# RFboardLeiden48_V_1_00.net
KiCad netlist of a schematic drawn in EAGLE
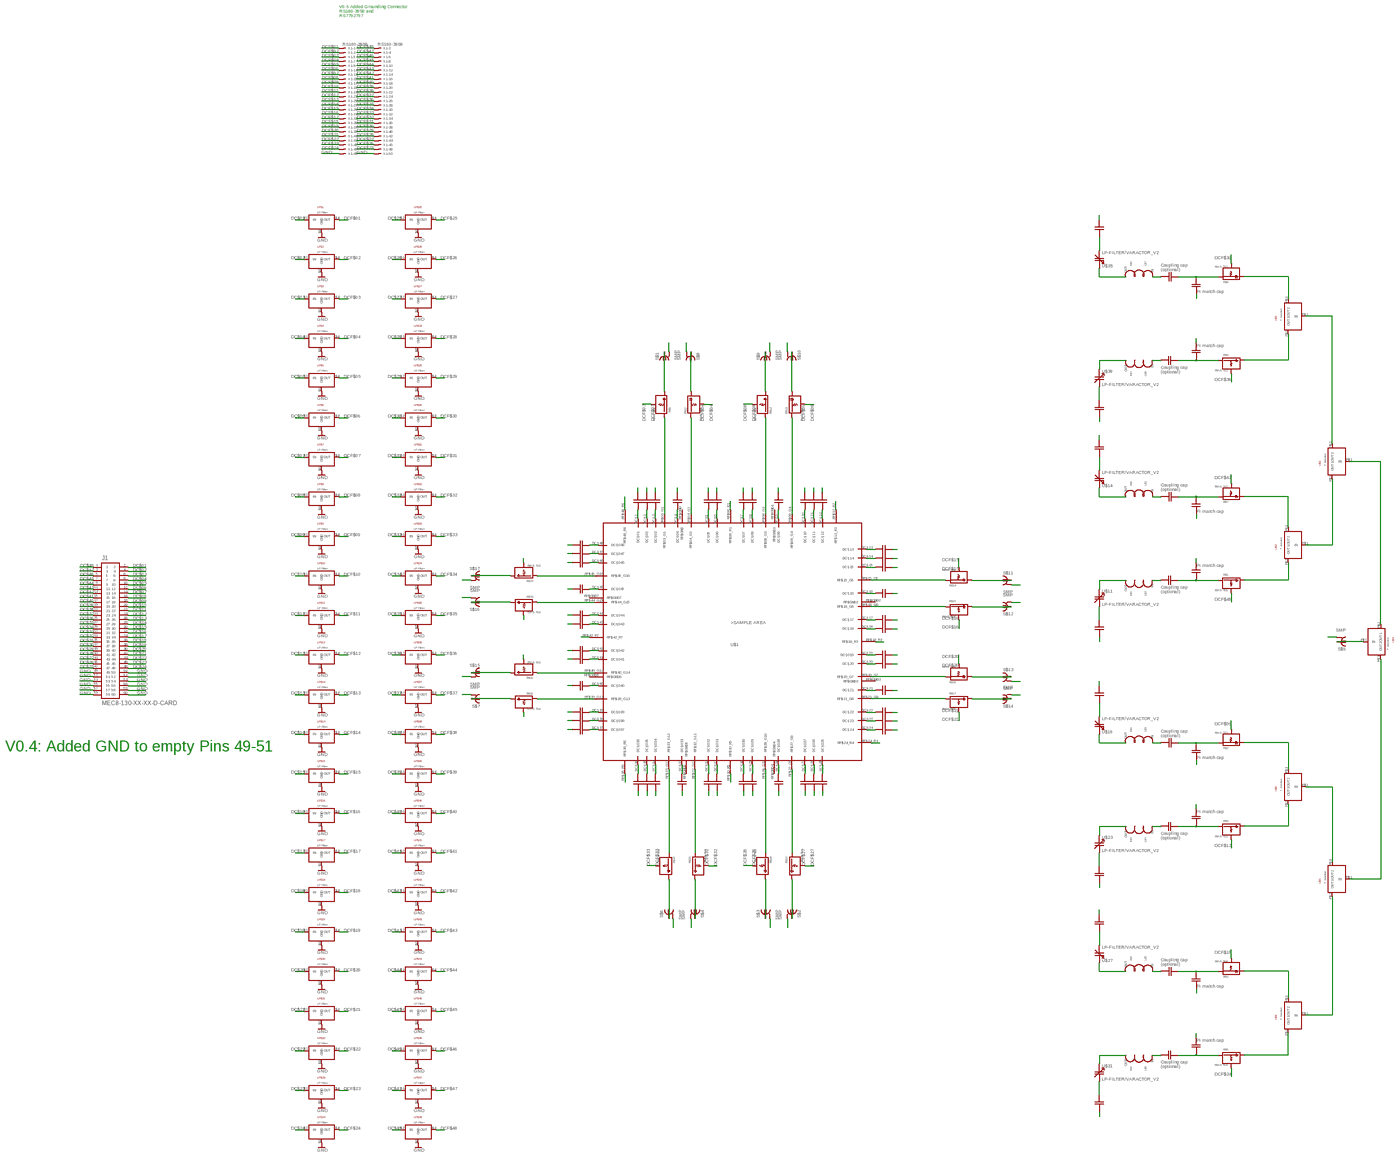
[diagram p0: schematic, sheet 1, overview]
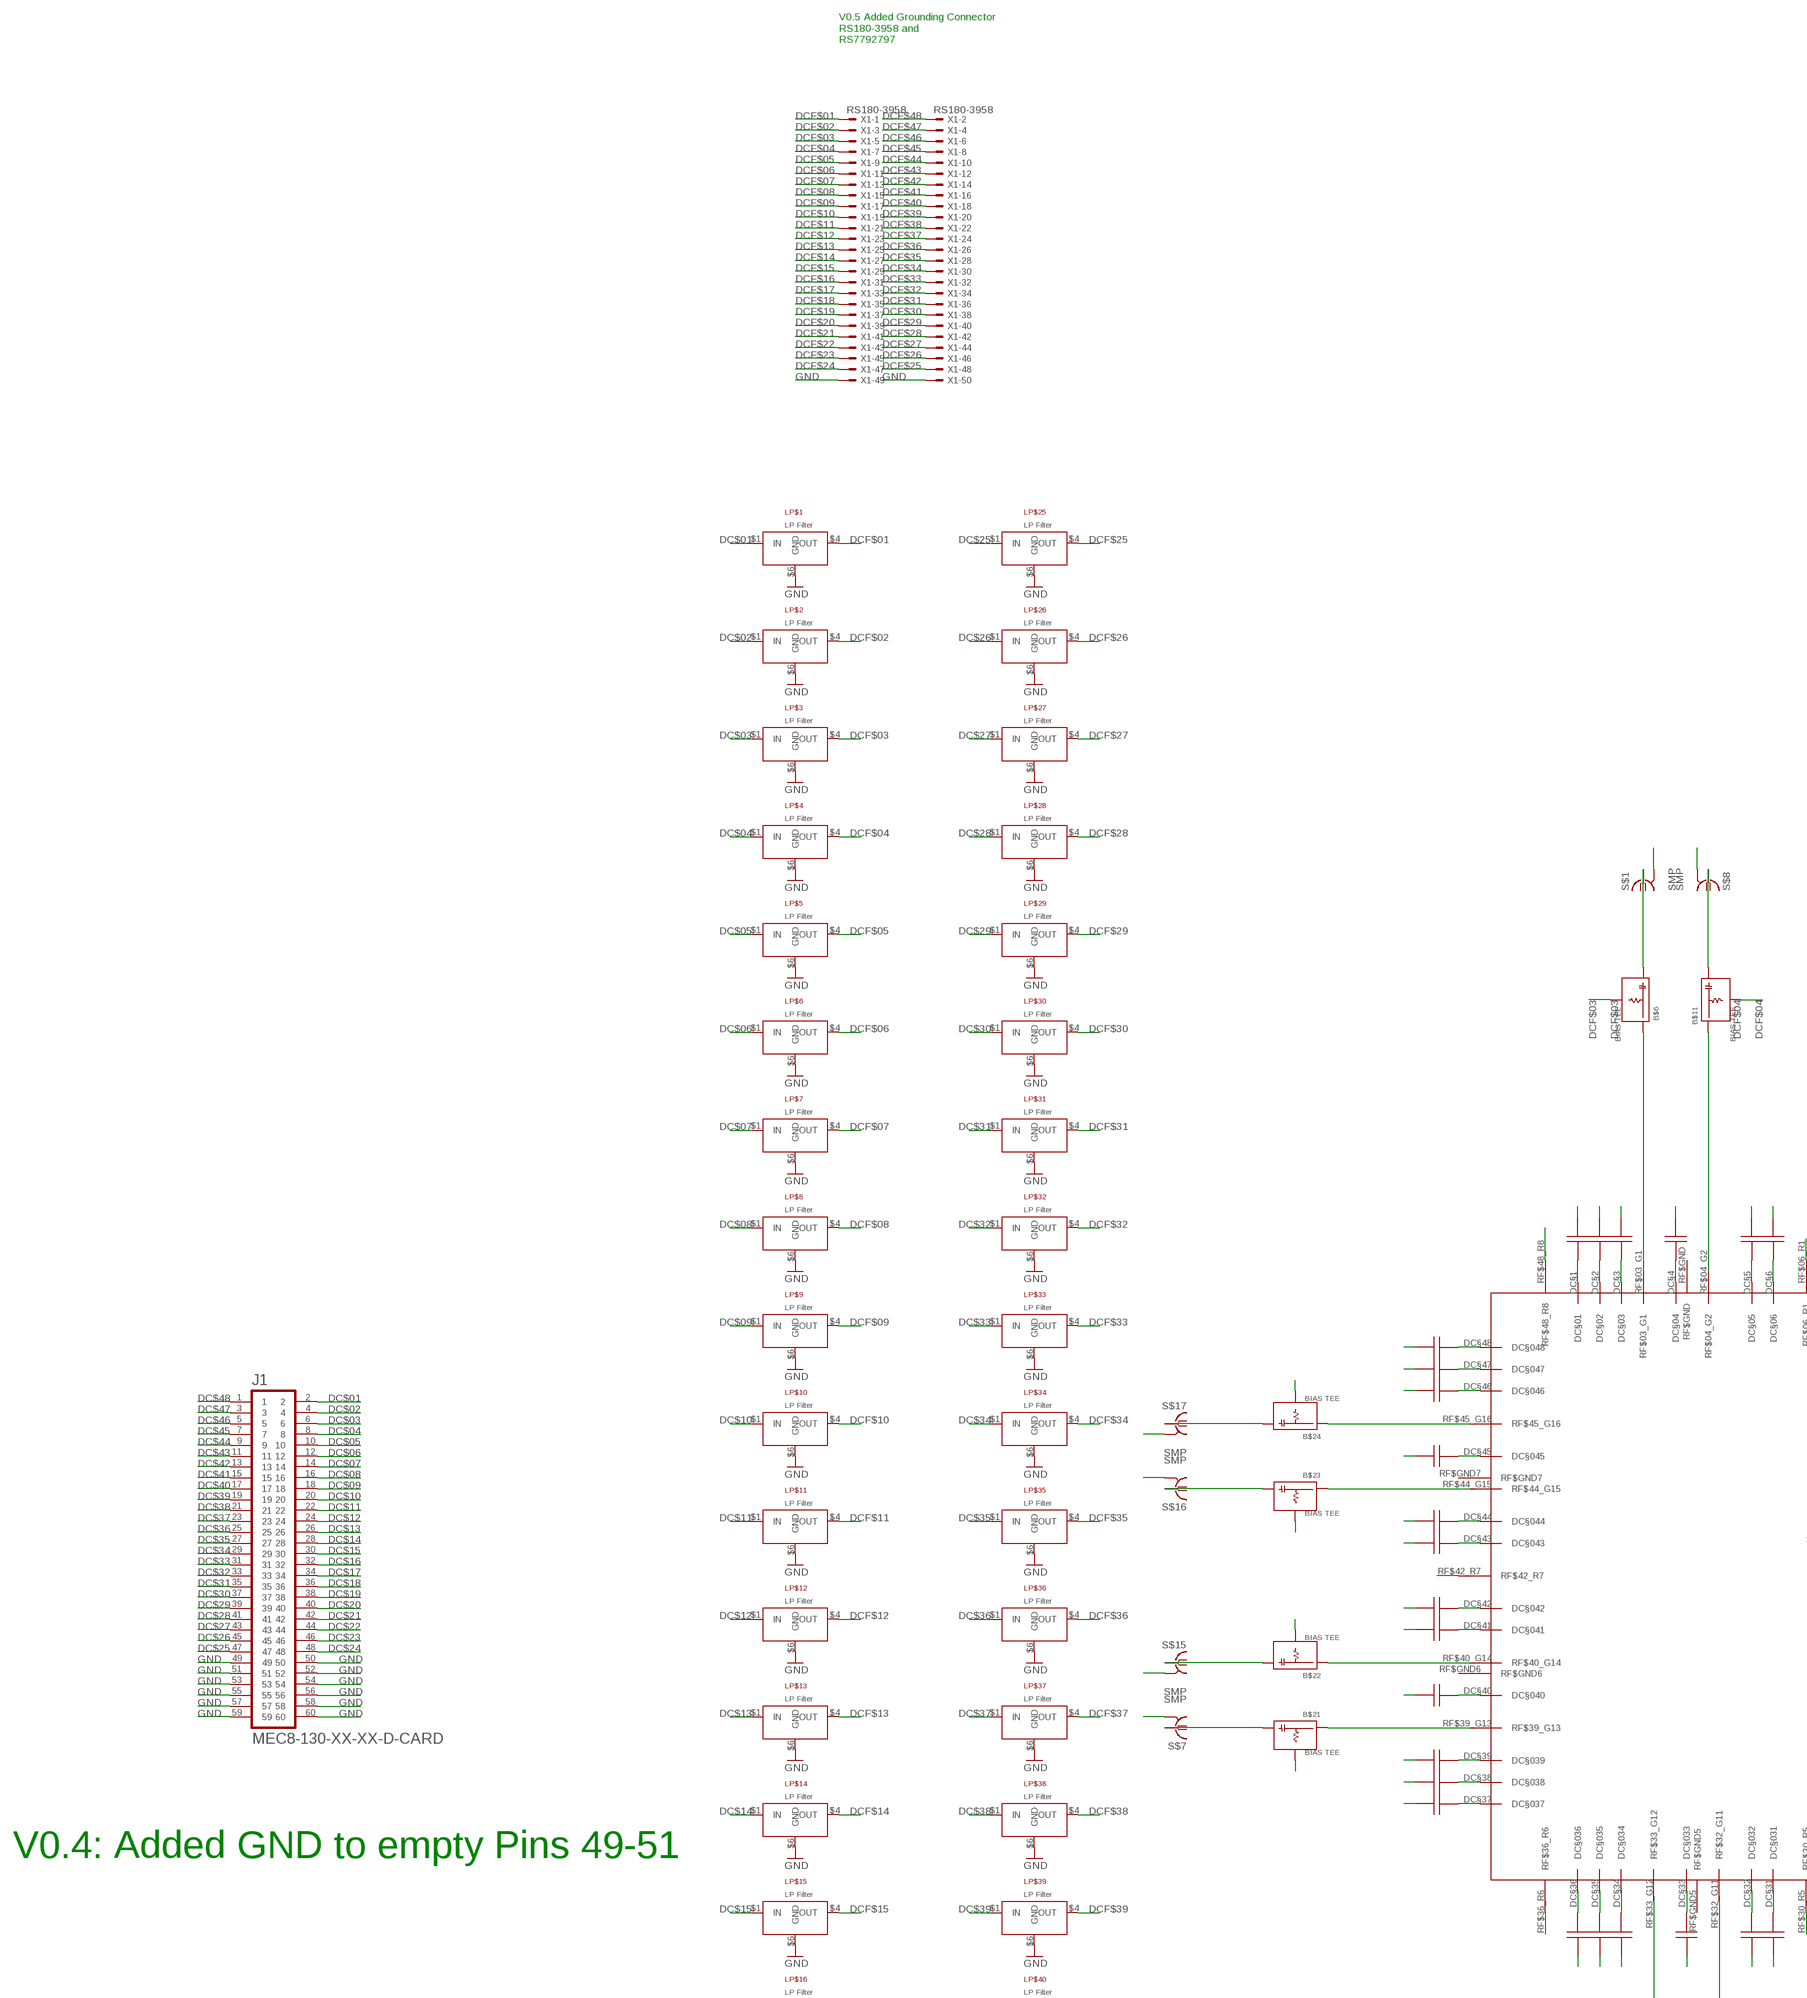
[diagram p1: schematic, sheet 1, part 1 of 4]
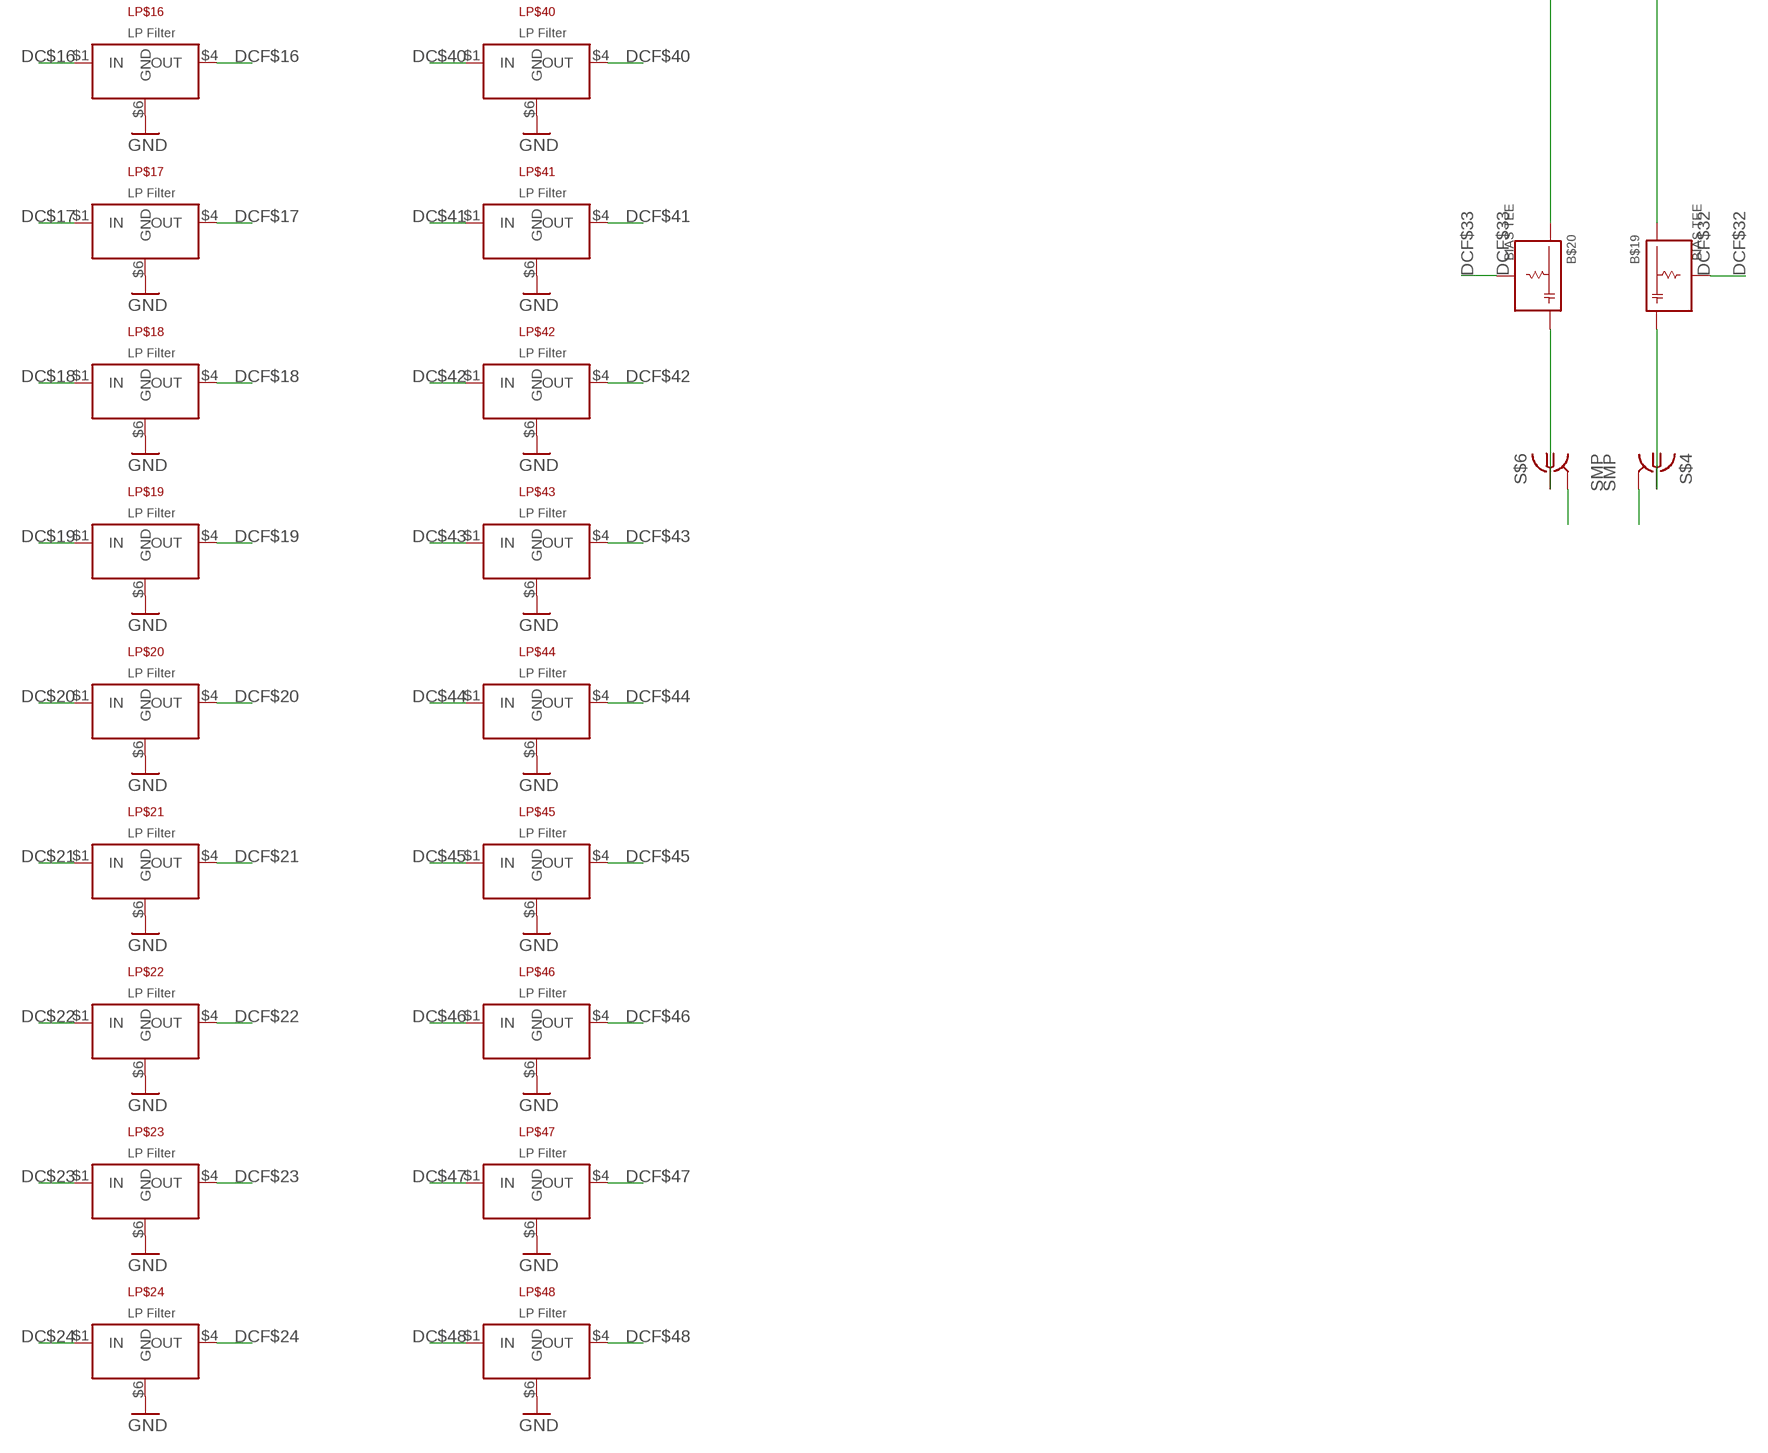
[diagram p2: schematic, sheet 1, part 2 of 4]
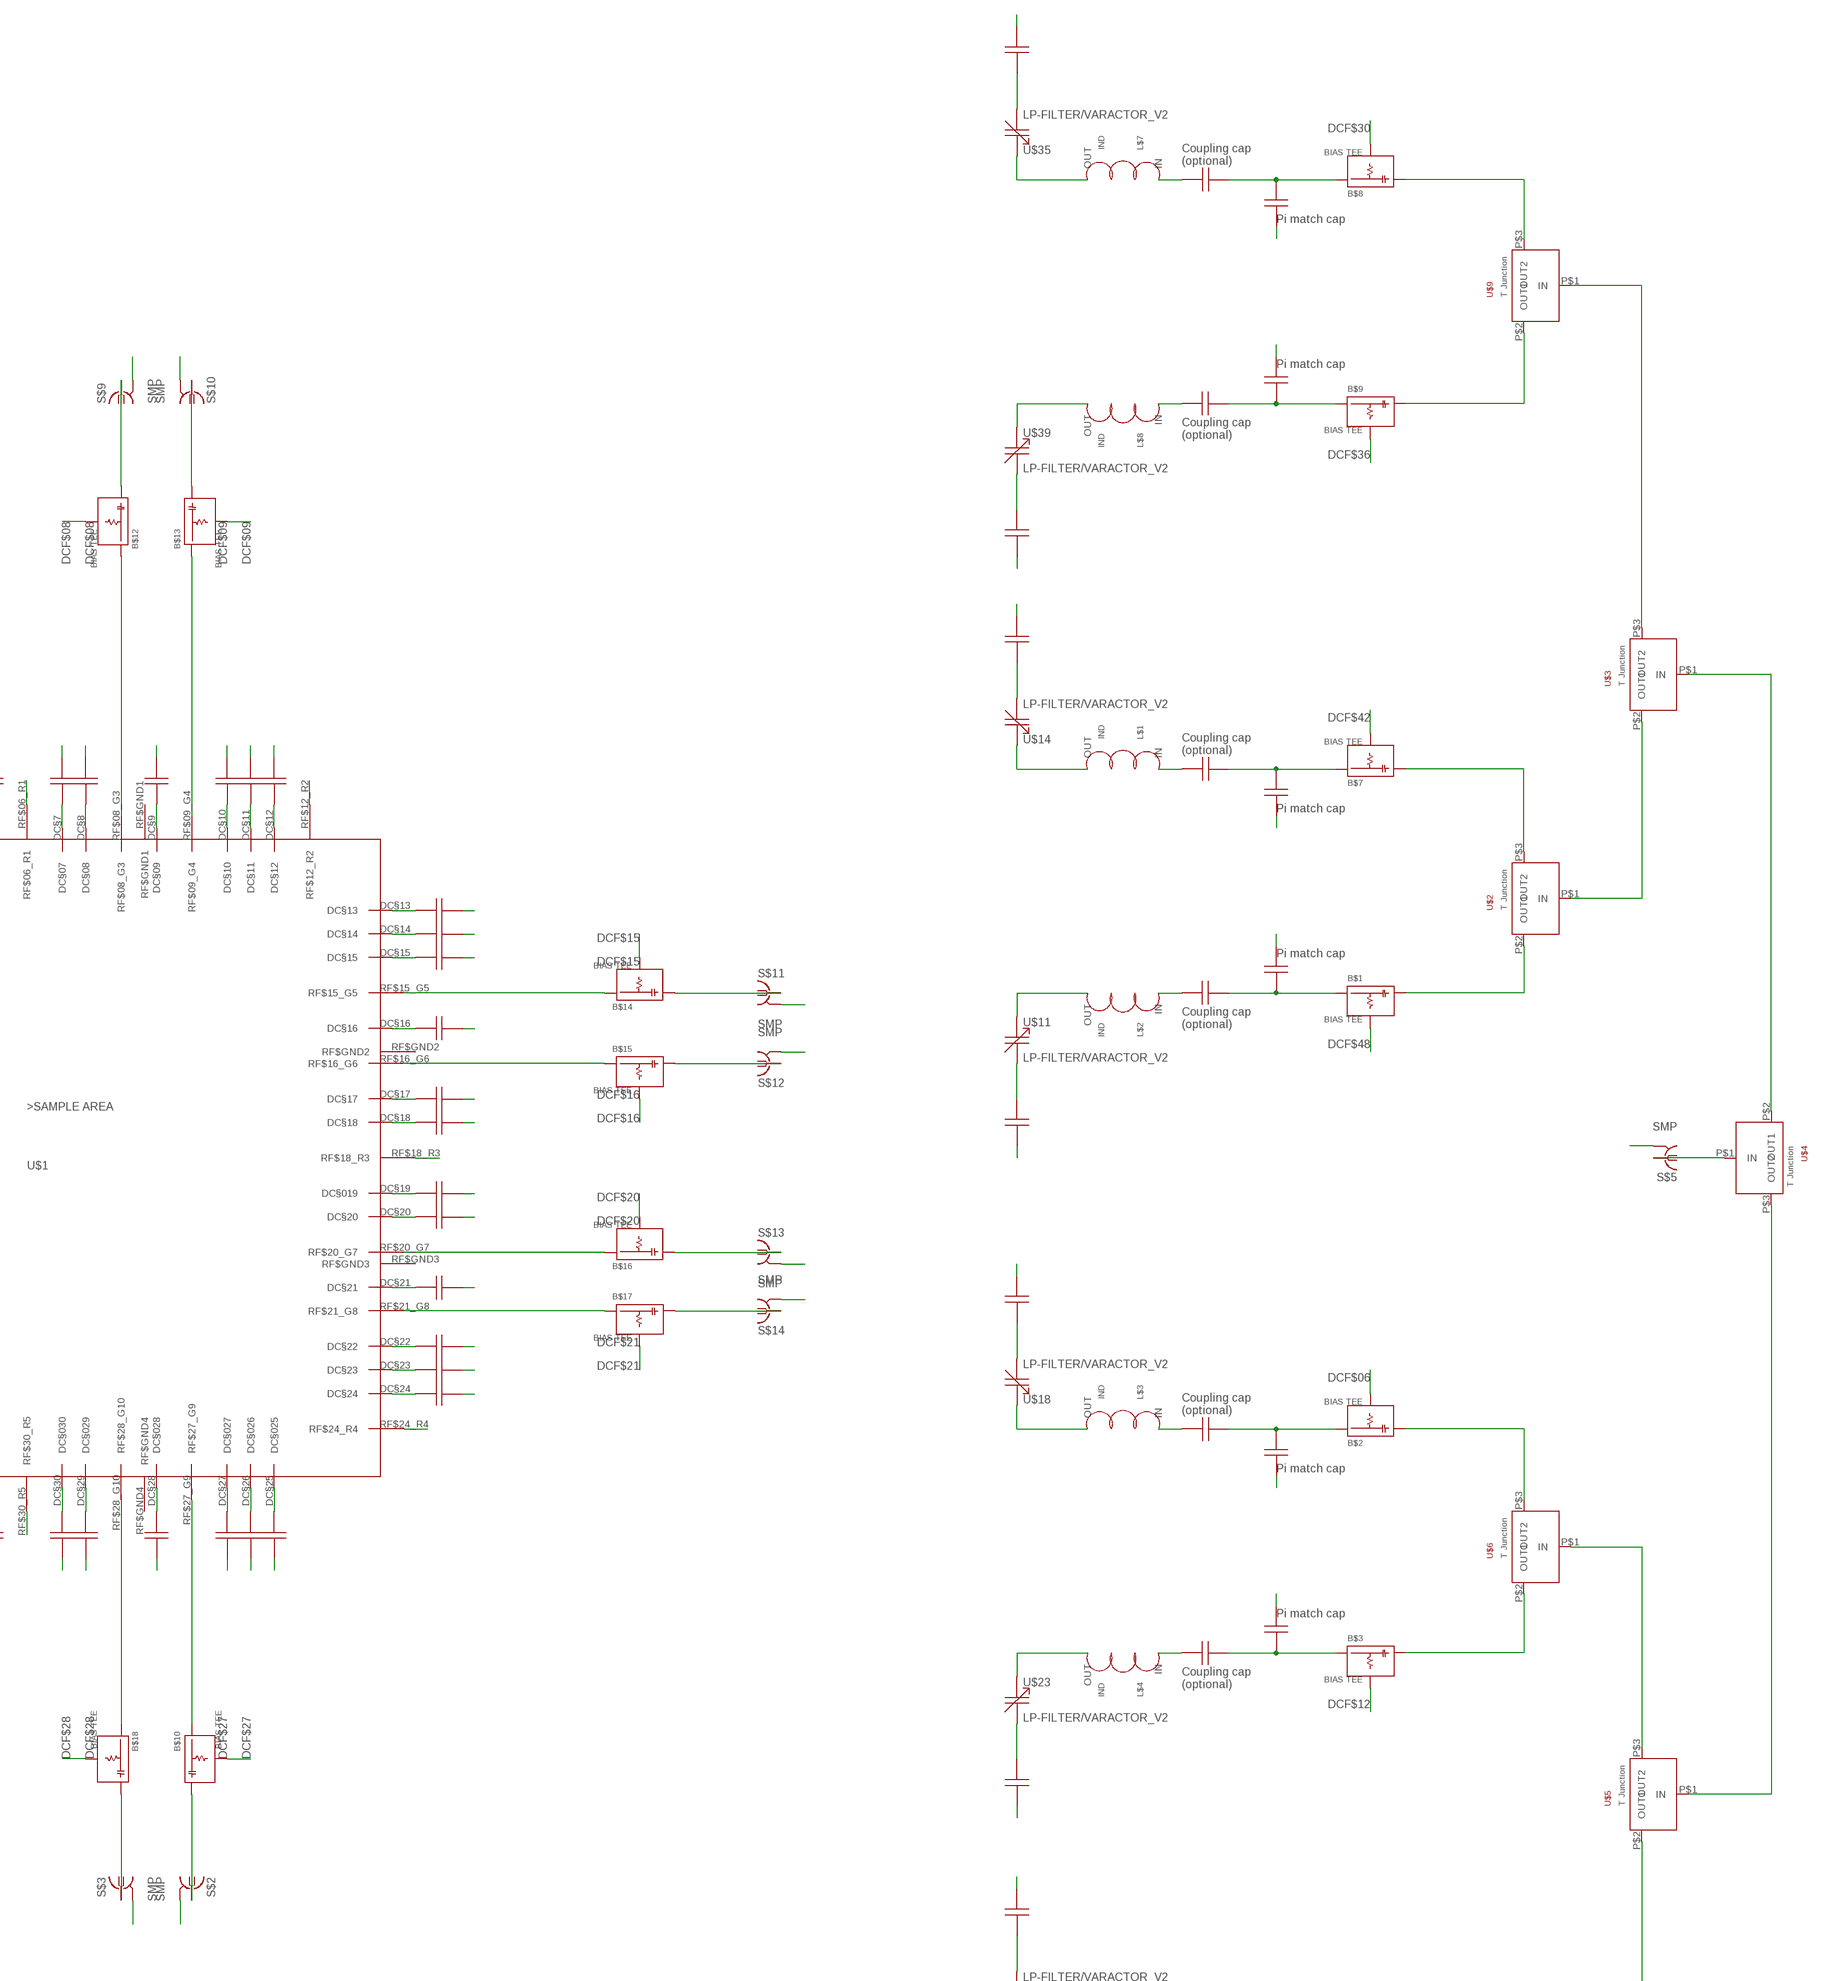
[diagram p3: schematic, sheet 1, part 3 of 4]
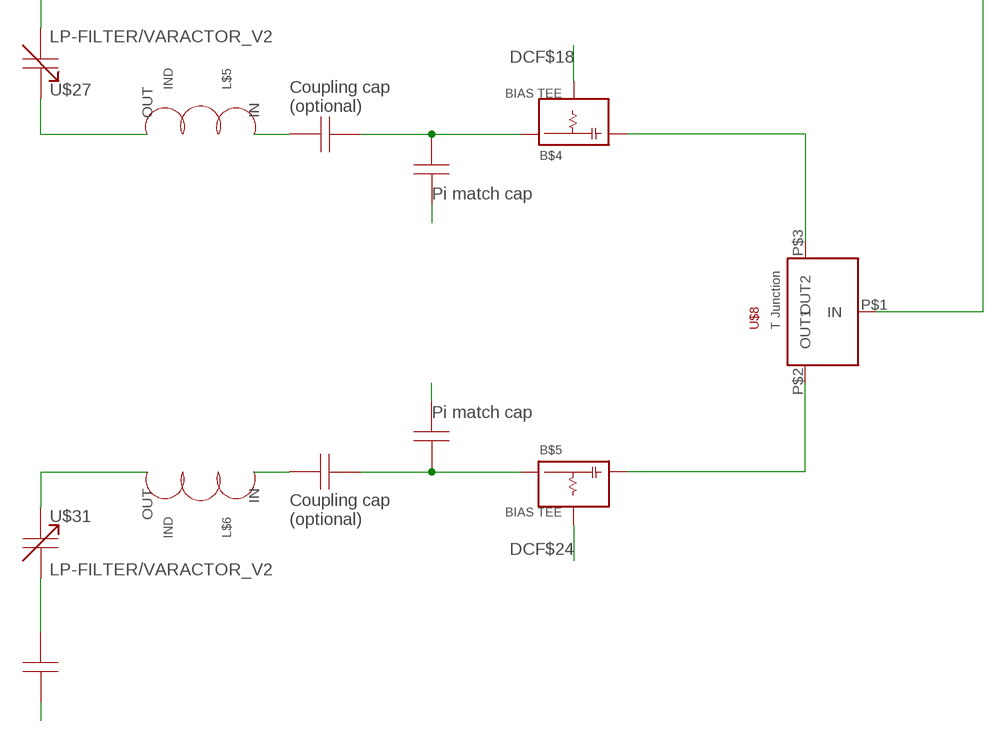
[diagram p4: schematic, sheet 1, part 4 of 4]

(export (version "E")
  (design (tool "Eeschema 10.0.6"))
  (components
    (comp (ref "B$1")
      (value "BIASTEEUP1")
      (footprint "eagle-import:BIAS_TEE_UP_0603")
      (libsource (lib "eagle-import") (part "BIASTEEUP1"))
    )
    (comp (ref "B$2")
      (value "BIASTEEUP1")
      (footprint "eagle-import:BIAS_TEE_UP_0603")
      (libsource (lib "eagle-import") (part "BIASTEEUP1"))
    )
    (comp (ref "B$3")
      (value "BIASTEEUP1")
      (footprint "eagle-import:BIAS_TEE_UP_0603")
      (libsource (lib "eagle-import") (part "BIASTEEUP1"))
    )
    (comp (ref "B$4")
      (value "BIASTEEUP1")
      (footprint "eagle-import:BIAS_TEE_UP_0603")
      (libsource (lib "eagle-import") (part "BIASTEEUP1"))
    )
    (comp (ref "B$5")
      (value "BIASTEEUP1")
      (footprint "eagle-import:BIAS_TEE_UP_0603")
      (libsource (lib "eagle-import") (part "BIASTEEUP1"))
    )
    (comp (ref "B$6")
      (value "BIASTEEDOWN1")
      (footprint "eagle-import:BIAS_TEE_DOWN_0603")
      (libsource (lib "eagle-import") (part "BIASTEEDOWN1"))
    )
    (comp (ref "B$7")
      (value "BIASTEEUP1")
      (footprint "eagle-import:BIAS_TEE_UP_0603")
      (libsource (lib "eagle-import") (part "BIASTEEUP1"))
    )
    (comp (ref "B$8")
      (value "BIASTEEUP1")
      (footprint "eagle-import:BIAS_TEE_UP_0603")
      (libsource (lib "eagle-import") (part "BIASTEEUP1"))
    )
    (comp (ref "B$9")
      (value "BIASTEEUP1")
      (footprint "eagle-import:BIAS_TEE_UP_0603")
      (libsource (lib "eagle-import") (part "BIASTEEUP1"))
    )
    (comp (ref "B$10")
      (value "BIASTEEDOWN1")
      (footprint "eagle-import:BIAS_TEE_DOWN_0603")
      (libsource (lib "eagle-import") (part "BIASTEEDOWN1"))
    )
    (comp (ref "B$11")
      (value "BIASTEEDOWN1")
      (footprint "eagle-import:BIAS_TEE_DOWN_0603")
      (libsource (lib "eagle-import") (part "BIASTEEDOWN1"))
    )
    (comp (ref "B$12")
      (value "BIASTEEUP1")
      (footprint "eagle-import:BIAS_TEE_UP_0603")
      (libsource (lib "eagle-import") (part "BIASTEEUP1"))
    )
    (comp (ref "B$13")
      (value "BIASTEEUP1")
      (footprint "eagle-import:BIAS_TEE_UP_0603")
      (libsource (lib "eagle-import") (part "BIASTEEUP1"))
    )
    (comp (ref "B$14")
      (value "BIASTEEDOWN1")
      (footprint "eagle-import:BIAS_TEE_DOWN_0603")
      (libsource (lib "eagle-import") (part "BIASTEEDOWN1"))
    )
    (comp (ref "B$15")
      (value "BIASTEEDOWN1")
      (footprint "eagle-import:BIAS_TEE_DOWN_0603")
      (libsource (lib "eagle-import") (part "BIASTEEDOWN1"))
    )
    (comp (ref "B$16")
      (value "BIASTEEUP1")
      (footprint "eagle-import:BIAS_TEE_UP_0603")
      (libsource (lib "eagle-import") (part "BIASTEEUP1"))
    )
    (comp (ref "B$17")
      (value "BIASTEEUP1")
      (footprint "eagle-import:BIAS_TEE_UP_0603")
      (libsource (lib "eagle-import") (part "BIASTEEUP1"))
    )
    (comp (ref "B$18")
      (value "BIASTEEDOWN1")
      (footprint "eagle-import:BIAS_TEE_DOWN_0603")
      (libsource (lib "eagle-import") (part "BIASTEEDOWN1"))
    )
    (comp (ref "B$19")
      (value "BIASTEEUP1")
      (footprint "eagle-import:BIAS_TEE_UP_0603")
      (libsource (lib "eagle-import") (part "BIASTEEUP1"))
    )
    (comp (ref "B$20")
      (value "BIASTEEUP1")
      (footprint "eagle-import:BIAS_TEE_UP_0603")
      (libsource (lib "eagle-import") (part "BIASTEEUP1"))
    )
    (comp (ref "B$21")
      (value "BIASTEEDOWN1")
      (footprint "eagle-import:BIAS_TEE_DOWN_0603")
      (libsource (lib "eagle-import") (part "BIASTEEDOWN1"))
    )
    (comp (ref "B$22")
      (value "BIASTEEDOWN1")
      (footprint "eagle-import:BIAS_TEE_DOWN_0603")
      (libsource (lib "eagle-import") (part "BIASTEEDOWN1"))
    )
    (comp (ref "B$23")
      (value "BIASTEEUP1")
      (footprint "eagle-import:BIAS_TEE_UP_0603")
      (libsource (lib "eagle-import") (part "BIASTEEUP1"))
    )
    (comp (ref "B$24")
      (value "BIASTEEUP1")
      (footprint "eagle-import:BIAS_TEE_UP_0603")
      (libsource (lib "eagle-import") (part "BIASTEEUP1"))
    )
    (comp (ref "J1")
      (value "MEC8-130-XX-XX-D-CARD")
      (footprint "eagle-import:SAMTEC_MEC8-130-XX-XX-D-CARD")
      (libsource (lib "eagle-import") (part "MEC8-130-XX-XX-D-CARD"))
    )
    (comp (ref "L$1")
      (value "L_MATCH")
      (footprint "eagle-import:L_MATCH")
      (libsource (lib "eagle-import") (part "L_MATCH"))
    )
    (comp (ref "L$2")
      (value "L_MATCH")
      (footprint "eagle-import:L_MATCH")
      (libsource (lib "eagle-import") (part "L_MATCH"))
    )
    (comp (ref "L$3")
      (value "L_MATCH")
      (footprint "eagle-import:L_MATCH")
      (libsource (lib "eagle-import") (part "L_MATCH"))
    )
    (comp (ref "L$4")
      (value "L_MATCH")
      (footprint "eagle-import:L_MATCH")
      (libsource (lib "eagle-import") (part "L_MATCH"))
    )
    (comp (ref "L$5")
      (value "L_MATCH")
      (footprint "eagle-import:L_MATCH")
      (libsource (lib "eagle-import") (part "L_MATCH"))
    )
    (comp (ref "L$6")
      (value "L_MATCH")
      (footprint "eagle-import:L_MATCH")
      (libsource (lib "eagle-import") (part "L_MATCH"))
    )
    (comp (ref "L$7")
      (value "L_MATCH")
      (footprint "eagle-import:L_MATCH")
      (libsource (lib "eagle-import") (part "L_MATCH"))
    )
    (comp (ref "L$8")
      (value "L_MATCH")
      (footprint "eagle-import:L_MATCH")
      (libsource (lib "eagle-import") (part "L_MATCH"))
    )
    (comp (ref "LP$1")
      (value "LP-FILTER/1-STAGETOP")
      (footprint "eagle-import:LP-FILTER_1_STAGE_OS_0603_TOP")
      (libsource (lib "eagle-import") (part "LP-FILTER/1-STAGETOP"))
    )
    (comp (ref "LP$2")
      (value "LP-FILTER/1-STAGETOP")
      (footprint "eagle-import:LP-FILTER_1_STAGE_OS_0603_TOP")
      (libsource (lib "eagle-import") (part "LP-FILTER/1-STAGETOP"))
    )
    (comp (ref "LP$3")
      (value "LP-FILTER/1-STAGETOP")
      (footprint "eagle-import:LP-FILTER_1_STAGE_OS_0603_TOP")
      (libsource (lib "eagle-import") (part "LP-FILTER/1-STAGETOP"))
    )
    (comp (ref "LP$4")
      (value "LP-FILTER/1-STAGETOP")
      (footprint "eagle-import:LP-FILTER_1_STAGE_OS_0603_TOP")
      (libsource (lib "eagle-import") (part "LP-FILTER/1-STAGETOP"))
    )
    (comp (ref "LP$5")
      (value "LP-FILTER/1-STAGETOP")
      (footprint "eagle-import:LP-FILTER_1_STAGE_OS_0603_TOP")
      (libsource (lib "eagle-import") (part "LP-FILTER/1-STAGETOP"))
    )
    (comp (ref "LP$6")
      (value "LP-FILTER/1-STAGETOP")
      (footprint "eagle-import:LP-FILTER_1_STAGE_OS_0603_TOP")
      (libsource (lib "eagle-import") (part "LP-FILTER/1-STAGETOP"))
    )
    (comp (ref "LP$7")
      (value "LP-FILTER/1-STAGETOP")
      (footprint "eagle-import:LP-FILTER_1_STAGE_OS_0603_TOP")
      (libsource (lib "eagle-import") (part "LP-FILTER/1-STAGETOP"))
    )
    (comp (ref "LP$8")
      (value "LP-FILTER/1-STAGETOP")
      (footprint "eagle-import:LP-FILTER_1_STAGE_OS_0603_TOP")
      (libsource (lib "eagle-import") (part "LP-FILTER/1-STAGETOP"))
    )
    (comp (ref "LP$9")
      (value "LP-FILTER/1-STAGETOP")
      (footprint "eagle-import:LP-FILTER_1_STAGE_OS_0603_TOP")
      (libsource (lib "eagle-import") (part "LP-FILTER/1-STAGETOP"))
    )
    (comp (ref "LP$10")
      (value "LP-FILTER/1-STAGETOP")
      (footprint "eagle-import:LP-FILTER_1_STAGE_OS_0603_TOP")
      (libsource (lib "eagle-import") (part "LP-FILTER/1-STAGETOP"))
    )
    (comp (ref "LP$11")
      (value "LP-FILTER/1-STAGETOP")
      (footprint "eagle-import:LP-FILTER_1_STAGE_OS_0603_TOP")
      (libsource (lib "eagle-import") (part "LP-FILTER/1-STAGETOP"))
    )
    (comp (ref "LP$12")
      (value "LP-FILTER/1-STAGETOP")
      (footprint "eagle-import:LP-FILTER_1_STAGE_OS_0603_TOP")
      (libsource (lib "eagle-import") (part "LP-FILTER/1-STAGETOP"))
    )
    (comp (ref "LP$13")
      (value "LP-FILTER/1-STAGETOP")
      (footprint "eagle-import:LP-FILTER_1_STAGE_OS_0603_TOP")
      (libsource (lib "eagle-import") (part "LP-FILTER/1-STAGETOP"))
    )
    (comp (ref "LP$14")
      (value "LP-FILTER/1-STAGETOP")
      (footprint "eagle-import:LP-FILTER_1_STAGE_OS_0603_TOP")
      (libsource (lib "eagle-import") (part "LP-FILTER/1-STAGETOP"))
    )
    (comp (ref "LP$15")
      (value "LP-FILTER/1-STAGETOP")
      (footprint "eagle-import:LP-FILTER_1_STAGE_OS_0603_TOP")
      (libsource (lib "eagle-import") (part "LP-FILTER/1-STAGETOP"))
    )
    (comp (ref "LP$16")
      (value "LP-FILTER/1-STAGETOP")
      (footprint "eagle-import:LP-FILTER_1_STAGE_OS_0603_TOP")
      (libsource (lib "eagle-import") (part "LP-FILTER/1-STAGETOP"))
    )
    (comp (ref "LP$17")
      (value "LP-FILTER/1-STAGETOP")
      (footprint "eagle-import:LP-FILTER_1_STAGE_OS_0603_TOP")
      (libsource (lib "eagle-import") (part "LP-FILTER/1-STAGETOP"))
    )
    (comp (ref "LP$18")
      (value "LP-FILTER/1-STAGETOP")
      (footprint "eagle-import:LP-FILTER_1_STAGE_OS_0603_TOP")
      (libsource (lib "eagle-import") (part "LP-FILTER/1-STAGETOP"))
    )
    (comp (ref "LP$19")
      (value "LP-FILTER/1-STAGETOP")
      (footprint "eagle-import:LP-FILTER_1_STAGE_OS_0603_TOP")
      (libsource (lib "eagle-import") (part "LP-FILTER/1-STAGETOP"))
    )
    (comp (ref "LP$20")
      (value "LP-FILTER/1-STAGETOP")
      (footprint "eagle-import:LP-FILTER_1_STAGE_OS_0603_TOP")
      (libsource (lib "eagle-import") (part "LP-FILTER/1-STAGETOP"))
    )
    (comp (ref "LP$21")
      (value "LP-FILTER/1-STAGETOP")
      (footprint "eagle-import:LP-FILTER_1_STAGE_OS_0603_TOP")
      (libsource (lib "eagle-import") (part "LP-FILTER/1-STAGETOP"))
    )
    (comp (ref "LP$22")
      (value "LP-FILTER/1-STAGETOP")
      (footprint "eagle-import:LP-FILTER_1_STAGE_OS_0603_TOP")
      (libsource (lib "eagle-import") (part "LP-FILTER/1-STAGETOP"))
    )
    (comp (ref "LP$23")
      (value "LP-FILTER/1-STAGETOP")
      (footprint "eagle-import:LP-FILTER_1_STAGE_OS_0603_TOP")
      (libsource (lib "eagle-import") (part "LP-FILTER/1-STAGETOP"))
    )
    (comp (ref "LP$24")
      (value "LP-FILTER/1-STAGETOP")
      (footprint "eagle-import:LP-FILTER_1_STAGE_OS_0603_TOP")
      (libsource (lib "eagle-import") (part "LP-FILTER/1-STAGETOP"))
    )
    (comp (ref "LP$25")
      (value "LP-FILTER/1-STAGETOP")
      (footprint "eagle-import:LP-FILTER_1_STAGE_OS_0603_TOP")
      (libsource (lib "eagle-import") (part "LP-FILTER/1-STAGETOP"))
    )
    (comp (ref "LP$26")
      (value "LP-FILTER/1-STAGETOP")
      (footprint "eagle-import:LP-FILTER_1_STAGE_OS_0603_TOP")
      (libsource (lib "eagle-import") (part "LP-FILTER/1-STAGETOP"))
    )
    (comp (ref "LP$27")
      (value "LP-FILTER/1-STAGETOP")
      (footprint "eagle-import:LP-FILTER_1_STAGE_OS_0603_TOP")
      (libsource (lib "eagle-import") (part "LP-FILTER/1-STAGETOP"))
    )
    (comp (ref "LP$28")
      (value "LP-FILTER/1-STAGETOP")
      (footprint "eagle-import:LP-FILTER_1_STAGE_OS_0603_TOP")
      (libsource (lib "eagle-import") (part "LP-FILTER/1-STAGETOP"))
    )
    (comp (ref "LP$29")
      (value "LP-FILTER/1-STAGETOP")
      (footprint "eagle-import:LP-FILTER_1_STAGE_OS_0603_TOP")
      (libsource (lib "eagle-import") (part "LP-FILTER/1-STAGETOP"))
    )
    (comp (ref "LP$30")
      (value "LP-FILTER/1-STAGETOP")
      (footprint "eagle-import:LP-FILTER_1_STAGE_OS_0603_TOP")
      (libsource (lib "eagle-import") (part "LP-FILTER/1-STAGETOP"))
    )
    (comp (ref "LP$31")
      (value "LP-FILTER/1-STAGETOP")
      (footprint "eagle-import:LP-FILTER_1_STAGE_OS_0603_TOP")
      (libsource (lib "eagle-import") (part "LP-FILTER/1-STAGETOP"))
    )
    (comp (ref "LP$32")
      (value "LP-FILTER/1-STAGETOP")
      (footprint "eagle-import:LP-FILTER_1_STAGE_OS_0603_TOP")
      (libsource (lib "eagle-import") (part "LP-FILTER/1-STAGETOP"))
    )
    (comp (ref "LP$33")
      (value "LP-FILTER/1-STAGETOP")
      (footprint "eagle-import:LP-FILTER_1_STAGE_OS_0603_TOP")
      (libsource (lib "eagle-import") (part "LP-FILTER/1-STAGETOP"))
    )
    (comp (ref "LP$34")
      (value "LP-FILTER/1-STAGETOP")
      (footprint "eagle-import:LP-FILTER_1_STAGE_OS_0603_TOP")
      (libsource (lib "eagle-import") (part "LP-FILTER/1-STAGETOP"))
    )
    (comp (ref "LP$35")
      (value "LP-FILTER/1-STAGETOP")
      (footprint "eagle-import:LP-FILTER_1_STAGE_OS_0603_TOP")
      (libsource (lib "eagle-import") (part "LP-FILTER/1-STAGETOP"))
    )
    (comp (ref "LP$36")
      (value "LP-FILTER/1-STAGETOP")
      (footprint "eagle-import:LP-FILTER_1_STAGE_OS_0603_TOP")
      (libsource (lib "eagle-import") (part "LP-FILTER/1-STAGETOP"))
    )
    (comp (ref "LP$37")
      (value "LP-FILTER/1-STAGETOP")
      (footprint "eagle-import:LP-FILTER_1_STAGE_OS_0603_TOP")
      (libsource (lib "eagle-import") (part "LP-FILTER/1-STAGETOP"))
    )
    (comp (ref "LP$38")
      (value "LP-FILTER/1-STAGETOP")
      (footprint "eagle-import:LP-FILTER_1_STAGE_OS_0603_TOP")
      (libsource (lib "eagle-import") (part "LP-FILTER/1-STAGETOP"))
    )
    (comp (ref "LP$39")
      (value "LP-FILTER/1-STAGETOP")
      (footprint "eagle-import:LP-FILTER_1_STAGE_OS_0603_TOP")
      (libsource (lib "eagle-import") (part "LP-FILTER/1-STAGETOP"))
    )
    (comp (ref "LP$40")
      (value "LP-FILTER/1-STAGETOP")
      (footprint "eagle-import:LP-FILTER_1_STAGE_OS_0603_TOP")
      (libsource (lib "eagle-import") (part "LP-FILTER/1-STAGETOP"))
    )
    (comp (ref "LP$41")
      (value "LP-FILTER/1-STAGETOP")
      (footprint "eagle-import:LP-FILTER_1_STAGE_OS_0603_TOP")
      (libsource (lib "eagle-import") (part "LP-FILTER/1-STAGETOP"))
    )
    (comp (ref "LP$42")
      (value "LP-FILTER/1-STAGETOP")
      (footprint "eagle-import:LP-FILTER_1_STAGE_OS_0603_TOP")
      (libsource (lib "eagle-import") (part "LP-FILTER/1-STAGETOP"))
    )
    (comp (ref "LP$43")
      (value "LP-FILTER/1-STAGETOP")
      (footprint "eagle-import:LP-FILTER_1_STAGE_OS_0603_TOP")
      (libsource (lib "eagle-import") (part "LP-FILTER/1-STAGETOP"))
    )
    (comp (ref "LP$44")
      (value "LP-FILTER/1-STAGETOP")
      (footprint "eagle-import:LP-FILTER_1_STAGE_OS_0603_TOP")
      (libsource (lib "eagle-import") (part "LP-FILTER/1-STAGETOP"))
    )
    (comp (ref "LP$45")
      (value "LP-FILTER/1-STAGETOP")
      (footprint "eagle-import:LP-FILTER_1_STAGE_OS_0603_TOP")
      (libsource (lib "eagle-import") (part "LP-FILTER/1-STAGETOP"))
    )
    (comp (ref "LP$46")
      (value "LP-FILTER/1-STAGETOP")
      (footprint "eagle-import:LP-FILTER_1_STAGE_OS_0603_TOP")
      (libsource (lib "eagle-import") (part "LP-FILTER/1-STAGETOP"))
    )
    (comp (ref "LP$47")
      (value "LP-FILTER/1-STAGETOP")
      (footprint "eagle-import:LP-FILTER_1_STAGE_OS_0603_TOP")
      (libsource (lib "eagle-import") (part "LP-FILTER/1-STAGETOP"))
    )
    (comp (ref "LP$48")
      (value "LP-FILTER/1-STAGETOP")
      (footprint "eagle-import:LP-FILTER_1_STAGE_OS_0603_TOP")
      (libsource (lib "eagle-import") (part "LP-FILTER/1-STAGETOP"))
    )
    (comp (ref "S$1")
      (value "MC-921WIDE")
      (footprint "eagle-import:SMP_STRAIGHT_MINI_WIDE")
      (libsource (lib "eagle-import") (part "MC-921WIDE"))
    )
    (comp (ref "S$2")
      (value "MC-921WIDE")
      (footprint "eagle-import:SMP_STRAIGHT_MINI_WIDE")
      (libsource (lib "eagle-import") (part "MC-921WIDE"))
    )
    (comp (ref "S$3")
      (value "MC-921WIDE")
      (footprint "eagle-import:SMP_STRAIGHT_MINI_WIDE")
      (libsource (lib "eagle-import") (part "MC-921WIDE"))
    )
    (comp (ref "S$4")
      (value "MC-921WIDE")
      (footprint "eagle-import:SMP_STRAIGHT_MINI_WIDE")
      (libsource (lib "eagle-import") (part "MC-921WIDE"))
    )
    (comp (ref "S$5")
      (value "MC-921WIDE")
      (footprint "eagle-import:SMP_STRAIGHT_MINI_WIDE")
      (libsource (lib "eagle-import") (part "MC-921WIDE"))
    )
    (comp (ref "S$6")
      (value "MC-921WIDE")
      (footprint "eagle-import:SMP_STRAIGHT_MINI_WIDE")
      (libsource (lib "eagle-import") (part "MC-921WIDE"))
    )
    (comp (ref "S$7")
      (value "MC-921WIDE")
      (footprint "eagle-import:SMP_STRAIGHT_MINI_WIDE")
      (libsource (lib "eagle-import") (part "MC-921WIDE"))
    )
    (comp (ref "S$8")
      (value "MC-921WIDE")
      (footprint "eagle-import:SMP_STRAIGHT_MINI_WIDE")
      (libsource (lib "eagle-import") (part "MC-921WIDE"))
    )
    (comp (ref "S$9")
      (value "MC-921WIDE")
      (footprint "eagle-import:SMP_STRAIGHT_MINI_WIDE")
      (libsource (lib "eagle-import") (part "MC-921WIDE"))
    )
    (comp (ref "S$10")
      (value "MC-921WIDE")
      (footprint "eagle-import:SMP_STRAIGHT_MINI_WIDE")
      (libsource (lib "eagle-import") (part "MC-921WIDE"))
    )
    (comp (ref "S$11")
      (value "MC-921WIDE")
      (footprint "eagle-import:SMP_STRAIGHT_MINI_WIDE")
      (libsource (lib "eagle-import") (part "MC-921WIDE"))
    )
    (comp (ref "S$12")
      (value "MC-921WIDE")
      (footprint "eagle-import:SMP_STRAIGHT_MINI_WIDE")
      (libsource (lib "eagle-import") (part "MC-921WIDE"))
    )
    (comp (ref "S$13")
      (value "MC-921WIDE")
      (footprint "eagle-import:SMP_STRAIGHT_MINI_WIDE")
      (libsource (lib "eagle-import") (part "MC-921WIDE"))
    )
    (comp (ref "S$14")
      (value "MC-921WIDE")
      (footprint "eagle-import:SMP_STRAIGHT_MINI_WIDE")
      (libsource (lib "eagle-import") (part "MC-921WIDE"))
    )
    (comp (ref "S$15")
      (value "MC-921WIDE")
      (footprint "eagle-import:SMP_STRAIGHT_MINI_WIDE")
      (libsource (lib "eagle-import") (part "MC-921WIDE"))
    )
    (comp (ref "S$16")
      (value "MC-921WIDE")
      (footprint "eagle-import:SMP_STRAIGHT_MINI_WIDE")
      (libsource (lib "eagle-import") (part "MC-921WIDE"))
    )
    (comp (ref "S$17")
      (value "MC-921WIDE")
      (footprint "eagle-import:SMP_STRAIGHT_MINI_WIDE")
      (libsource (lib "eagle-import") (part "MC-921WIDE"))
    )
    (comp (ref "U$1")
      (value "48DC+24RF_V3.0")
      (footprint "eagle-import:48DC+24RF_V3.0")
      (libsource (lib "eagle-import") (part "48DC+24RF_V3.0"))
    )
    (comp (ref "U$2")
      (value "TJUNCTION")
      (footprint "eagle-import:T_JUNCTION_0.3MM")
      (libsource (lib "eagle-import") (part "TJUNCTION"))
    )
    (comp (ref "U$3")
      (value "TJUNCTION")
      (footprint "eagle-import:T_JUNCTION_0.3MM")
      (libsource (lib "eagle-import") (part "TJUNCTION"))
    )
    (comp (ref "U$4")
      (value "TJUNCTION")
      (footprint "eagle-import:T_JUNCTION_0.3MM")
      (libsource (lib "eagle-import") (part "TJUNCTION"))
    )
    (comp (ref "U$5")
      (value "TJUNCTION")
      (footprint "eagle-import:T_JUNCTION_0.3MM")
      (libsource (lib "eagle-import") (part "TJUNCTION"))
    )
    (comp (ref "U$6")
      (value "TJUNCTION")
      (footprint "eagle-import:T_JUNCTION_0.3MM")
      (libsource (lib "eagle-import") (part "TJUNCTION"))
    )
    (comp (ref "U$7")
      (value "LP-FILTER/CAPACITOR/0603THIN")
      (footprint "eagle-import:LP-FILTER_CAPACITOR_0603_BOTTOM")
      (libsource (lib "eagle-import") (part "LP-FILTER/CAPACITOR/0603THIN"))
    )
    (comp (ref "U$8")
      (value "TJUNCTION")
      (footprint "eagle-import:T_JUNCTION_0.3MM")
      (libsource (lib "eagle-import") (part "TJUNCTION"))
    )
    (comp (ref "U$9")
      (value "TJUNCTION")
      (footprint "eagle-import:T_JUNCTION_0.3MM")
      (libsource (lib "eagle-import") (part "TJUNCTION"))
    )
    (comp (ref "U$10")
      (value "LP-FILTER/CAPACITOR/0603THIN")
      (footprint "eagle-import:LP-FILTER_CAPACITOR_0603_BOTTOM")
      (libsource (lib "eagle-import") (part "LP-FILTER/CAPACITOR/0603THIN"))
    )
    (comp (ref "U$11")
      (value "LP-FILTER/VARACTOR_V2")
      (footprint "eagle-import:LP-FILTER_VARACTOR_V2")
      (libsource (lib "eagle-import") (part "LP-FILTER/VARACTOR_V2"))
    )
    (comp (ref "U$12")
      (value "LP-FILTER/CAPACITOR/0603NORMAL")
      (footprint "eagle-import:LP-FILTER_CAPACITOR_0603_BOTTOM_V2")
      (libsource (lib "eagle-import") (part "LP-FILTER/CAPACITOR/0603NORMAL"))
    )
    (comp (ref "U$13")
      (value "LP-FILTER/CAPACITOR/0603THIN")
      (footprint "eagle-import:LP-FILTER_CAPACITOR_0603_BOTTOM")
      (libsource (lib "eagle-import") (part "LP-FILTER/CAPACITOR/0603THIN"))
    )
    (comp (ref "U$14")
      (value "LP-FILTER/VARACTOR_V2")
      (footprint "eagle-import:LP-FILTER_VARACTOR_V2")
      (libsource (lib "eagle-import") (part "LP-FILTER/VARACTOR_V2"))
    )
    (comp (ref "U$15")
      (value "LP-FILTER/CAPACITOR/0603NORMAL")
      (footprint "eagle-import:LP-FILTER_CAPACITOR_0603_BOTTOM_V2")
      (libsource (lib "eagle-import") (part "LP-FILTER/CAPACITOR/0603NORMAL"))
    )
    (comp (ref "U$16")
      (value "LP-FILTER/CAPACITOR/0603THIN")
      (footprint "eagle-import:LP-FILTER_CAPACITOR_0603_BOTTOM")
      (libsource (lib "eagle-import") (part "LP-FILTER/CAPACITOR/0603THIN"))
    )
    (comp (ref "U$17")
      (value "LP-FILTER/CAPACITOR/0603THIN")
      (footprint "eagle-import:LP-FILTER_CAPACITOR_0603_BOTTOM")
      (libsource (lib "eagle-import") (part "LP-FILTER/CAPACITOR/0603THIN"))
    )
    (comp (ref "U$18")
      (value "LP-FILTER/VARACTOR_V2")
      (footprint "eagle-import:LP-FILTER_VARACTOR_V2")
      (libsource (lib "eagle-import") (part "LP-FILTER/VARACTOR_V2"))
    )
    (comp (ref "U$19")
      (value "LP-FILTER/CAPACITOR/0603NORMAL")
      (footprint "eagle-import:LP-FILTER_CAPACITOR_0603_BOTTOM_V2")
      (libsource (lib "eagle-import") (part "LP-FILTER/CAPACITOR/0603NORMAL"))
    )
    (comp (ref "U$20")
      (value "LP-FILTER/CAPACITOR/0603THIN")
      (footprint "eagle-import:LP-FILTER_CAPACITOR_0603_BOTTOM")
      (libsource (lib "eagle-import") (part "LP-FILTER/CAPACITOR/0603THIN"))
    )
    (comp (ref "U$21")
      (value "LP-FILTER/CAPACITOR/0603THIN")
      (footprint "eagle-import:LP-FILTER_CAPACITOR_0603_BOTTOM")
      (libsource (lib "eagle-import") (part "LP-FILTER/CAPACITOR/0603THIN"))
    )
    (comp (ref "U$22")
      (value "LP-FILTER/CAPACITOR/0603THIN")
      (footprint "eagle-import:LP-FILTER_CAPACITOR_0603_BOTTOM")
      (libsource (lib "eagle-import") (part "LP-FILTER/CAPACITOR/0603THIN"))
    )
    (comp (ref "U$23")
      (value "LP-FILTER/VARACTOR_V2")
      (footprint "eagle-import:LP-FILTER_VARACTOR_V2")
      (libsource (lib "eagle-import") (part "LP-FILTER/VARACTOR_V2"))
    )
    (comp (ref "U$24")
      (value "LP-FILTER/CAPACITOR/0603NORMAL")
      (footprint "eagle-import:LP-FILTER_CAPACITOR_0603_BOTTOM_V2")
      (libsource (lib "eagle-import") (part "LP-FILTER/CAPACITOR/0603NORMAL"))
    )
    (comp (ref "U$26")
      (value "LP-FILTER/CAPACITOR/0603THIN")
      (footprint "eagle-import:LP-FILTER_CAPACITOR_0603_BOTTOM")
      (libsource (lib "eagle-import") (part "LP-FILTER/CAPACITOR/0603THIN"))
    )
    (comp (ref "U$27")
      (value "LP-FILTER/VARACTOR_V2")
      (footprint "eagle-import:LP-FILTER_VARACTOR_V2")
      (libsource (lib "eagle-import") (part "LP-FILTER/VARACTOR_V2"))
    )
    (comp (ref "U$28")
      (value "LP-FILTER/CAPACITOR/0603NORMAL")
      (footprint "eagle-import:LP-FILTER_CAPACITOR_0603_BOTTOM_V2")
      (libsource (lib "eagle-import") (part "LP-FILTER/CAPACITOR/0603NORMAL"))
    )
    (comp (ref "U$29")
      (value "LP-FILTER/CAPACITOR/0603THIN")
      (footprint "eagle-import:LP-FILTER_CAPACITOR_0603_BOTTOM")
      (libsource (lib "eagle-import") (part "LP-FILTER/CAPACITOR/0603THIN"))
    )
    (comp (ref "U$30")
      (value "LP-FILTER/CAPACITOR/0603THIN")
      (footprint "eagle-import:LP-FILTER_CAPACITOR_0603_BOTTOM")
      (libsource (lib "eagle-import") (part "LP-FILTER/CAPACITOR/0603THIN"))
    )
    (comp (ref "U$31")
      (value "LP-FILTER/VARACTOR_V2")
      (footprint "eagle-import:LP-FILTER_VARACTOR_V2")
      (libsource (lib "eagle-import") (part "LP-FILTER/VARACTOR_V2"))
    )
    (comp (ref "U$32")
      (value "LP-FILTER/CAPACITOR/0603NORMAL")
      (footprint "eagle-import:LP-FILTER_CAPACITOR_0603_BOTTOM_V2")
      (libsource (lib "eagle-import") (part "LP-FILTER/CAPACITOR/0603NORMAL"))
    )
    (comp (ref "U$33")
      (value "LP-FILTER/CAPACITOR/0603THIN")
      (footprint "eagle-import:LP-FILTER_CAPACITOR_0603_BOTTOM")
      (libsource (lib "eagle-import") (part "LP-FILTER/CAPACITOR/0603THIN"))
    )
    (comp (ref "U$34")
      (value "LP-FILTER/CAPACITOR/0603THIN")
      (footprint "eagle-import:LP-FILTER_CAPACITOR_0603_BOTTOM")
      (libsource (lib "eagle-import") (part "LP-FILTER/CAPACITOR/0603THIN"))
    )
    (comp (ref "U$35")
      (value "LP-FILTER/VARACTOR_V2")
      (footprint "eagle-import:LP-FILTER_VARACTOR_V2")
      (libsource (lib "eagle-import") (part "LP-FILTER/VARACTOR_V2"))
    )
    (comp (ref "U$36")
      (value "LP-FILTER/CAPACITOR/0603NORMAL")
      (footprint "eagle-import:LP-FILTER_CAPACITOR_0603_BOTTOM_V2")
      (libsource (lib "eagle-import") (part "LP-FILTER/CAPACITOR/0603NORMAL"))
    )
    (comp (ref "U$37")
      (value "LP-FILTER/CAPACITOR/0603THIN")
      (footprint "eagle-import:LP-FILTER_CAPACITOR_0603_BOTTOM")
      (libsource (lib "eagle-import") (part "LP-FILTER/CAPACITOR/0603THIN"))
    )
    (comp (ref "U$38")
      (value "LP-FILTER/CAPACITOR/0603THIN")
      (footprint "eagle-import:LP-FILTER_CAPACITOR_0603_BOTTOM")
      (libsource (lib "eagle-import") (part "LP-FILTER/CAPACITOR/0603THIN"))
    )
    (comp (ref "U$39")
      (value "LP-FILTER/VARACTOR_V2")
      (footprint "eagle-import:LP-FILTER_VARACTOR_V2")
      (libsource (lib "eagle-import") (part "LP-FILTER/VARACTOR_V2"))
    )
    (comp (ref "U$40")
      (value "LP-FILTER/CAPACITOR/0603NORMAL")
      (footprint "eagle-import:LP-FILTER_CAPACITOR_0603_BOTTOM_V2")
      (libsource (lib "eagle-import") (part "LP-FILTER/CAPACITOR/0603NORMAL"))
    )
    (comp (ref "U$41")
      (value "LP-FILTER/CAPACITOR/0603THIN")
      (footprint "eagle-import:LP-FILTER_CAPACITOR_0603_BOTTOM")
      (libsource (lib "eagle-import") (part "LP-FILTER/CAPACITOR/0603THIN"))
    )
    (comp (ref "U$42")
      (value "LP-FILTER/CAPACITOR/0603THIN")
      (footprint "eagle-import:LP-FILTER_CAPACITOR_0603_BOTTOM")
      (libsource (lib "eagle-import") (part "LP-FILTER/CAPACITOR/0603THIN"))
    )
    (comp (ref "U$43")
      (value "LP-FILTER/CAPACITOR/0603THIN")
      (footprint "eagle-import:LP-FILTER_CAPACITOR_0603_BOTTOM")
      (libsource (lib "eagle-import") (part "LP-FILTER/CAPACITOR/0603THIN"))
    )
    (comp (ref "U$44")
      (value "LP-FILTER/CAPACITOR/0603THIN")
      (footprint "eagle-import:LP-FILTER_CAPACITOR_0603_BOTTOM")
      (libsource (lib "eagle-import") (part "LP-FILTER/CAPACITOR/0603THIN"))
    )
    (comp (ref "U$45")
      (value "LP-FILTER/CAPACITOR/0603THIN")
      (footprint "eagle-import:LP-FILTER_CAPACITOR_0603_BOTTOM")
      (libsource (lib "eagle-import") (part "LP-FILTER/CAPACITOR/0603THIN"))
    )
    (comp (ref "U$46")
      (value "LP-FILTER/CAPACITOR/0603THIN")
      (footprint "eagle-import:LP-FILTER_CAPACITOR_0603_BOTTOM")
      (libsource (lib "eagle-import") (part "LP-FILTER/CAPACITOR/0603THIN"))
    )
    (comp (ref "U$47")
      (value "LP-FILTER/CAPACITOR/0603THIN")
      (footprint "eagle-import:LP-FILTER_CAPACITOR_0603_BOTTOM")
      (libsource (lib "eagle-import") (part "LP-FILTER/CAPACITOR/0603THIN"))
    )
    (comp (ref "U$48")
      (value "LP-FILTER/CAPACITOR/0603THIN")
      (footprint "eagle-import:LP-FILTER_CAPACITOR_0603_BOTTOM")
      (libsource (lib "eagle-import") (part "LP-FILTER/CAPACITOR/0603THIN"))
    )
    (comp (ref "U$49")
      (value "LP-FILTER/CAPACITOR/0603THIN")
      (footprint "eagle-import:LP-FILTER_CAPACITOR_0603_BOTTOM")
      (libsource (lib "eagle-import") (part "LP-FILTER/CAPACITOR/0603THIN"))
    )
    (comp (ref "U$50")
      (value "LP-FILTER/CAPACITOR/0603THIN")
      (footprint "eagle-import:LP-FILTER_CAPACITOR_0603_BOTTOM")
      (libsource (lib "eagle-import") (part "LP-FILTER/CAPACITOR/0603THIN"))
    )
    (comp (ref "U$51")
      (value "LP-FILTER/CAPACITOR/0603THIN")
      (footprint "eagle-import:LP-FILTER_CAPACITOR_0603_BOTTOM")
      (libsource (lib "eagle-import") (part "LP-FILTER/CAPACITOR/0603THIN"))
    )
    (comp (ref "U$52")
      (value "LP-FILTER/CAPACITOR/0603THIN")
      (footprint "eagle-import:LP-FILTER_CAPACITOR_0603_BOTTOM")
      (libsource (lib "eagle-import") (part "LP-FILTER/CAPACITOR/0603THIN"))
    )
    (comp (ref "U$53")
      (value "LP-FILTER/CAPACITOR/0603THIN")
      (footprint "eagle-import:LP-FILTER_CAPACITOR_0603_BOTTOM")
      (libsource (lib "eagle-import") (part "LP-FILTER/CAPACITOR/0603THIN"))
    )
    (comp (ref "U$54")
      (value "LP-FILTER/CAPACITOR/0603THIN")
      (footprint "eagle-import:LP-FILTER_CAPACITOR_0603_BOTTOM")
      (libsource (lib "eagle-import") (part "LP-FILTER/CAPACITOR/0603THIN"))
    )
    (comp (ref "U$55")
      (value "LP-FILTER/CAPACITOR/0603THIN")
      (footprint "eagle-import:LP-FILTER_CAPACITOR_0603_BOTTOM")
      (libsource (lib "eagle-import") (part "LP-FILTER/CAPACITOR/0603THIN"))
    )
    (comp (ref "U$56")
      (value "LP-FILTER/CAPACITOR/0603THIN")
      (footprint "eagle-import:LP-FILTER_CAPACITOR_0603_BOTTOM")
      (libsource (lib "eagle-import") (part "LP-FILTER/CAPACITOR/0603THIN"))
    )
    (comp (ref "U$57")
      (value "LP-FILTER/CAPACITOR/0603THIN")
      (footprint "eagle-import:LP-FILTER_CAPACITOR_0603_BOTTOM")
      (libsource (lib "eagle-import") (part "LP-FILTER/CAPACITOR/0603THIN"))
    )
    (comp (ref "U$58")
      (value "LP-FILTER/CAPACITOR/0603THIN")
      (footprint "eagle-import:LP-FILTER_CAPACITOR_0603_BOTTOM")
      (libsource (lib "eagle-import") (part "LP-FILTER/CAPACITOR/0603THIN"))
    )
    (comp (ref "U$59")
      (value "LP-FILTER/CAPACITOR/0603THIN")
      (footprint "eagle-import:LP-FILTER_CAPACITOR_0603_BOTTOM")
      (libsource (lib "eagle-import") (part "LP-FILTER/CAPACITOR/0603THIN"))
    )
    (comp (ref "U$60")
      (value "LP-FILTER/CAPACITOR/0603THIN")
      (footprint "eagle-import:LP-FILTER_CAPACITOR_0603_BOTTOM")
      (libsource (lib "eagle-import") (part "LP-FILTER/CAPACITOR/0603THIN"))
    )
    (comp (ref "U$61")
      (value "LP-FILTER/CAPACITOR/0603THIN")
      (footprint "eagle-import:LP-FILTER_CAPACITOR_0603_BOTTOM")
      (libsource (lib "eagle-import") (part "LP-FILTER/CAPACITOR/0603THIN"))
    )
    (comp (ref "U$62")
      (value "LP-FILTER/CAPACITOR/0603THIN")
      (footprint "eagle-import:LP-FILTER_CAPACITOR_0603_BOTTOM")
      (libsource (lib "eagle-import") (part "LP-FILTER/CAPACITOR/0603THIN"))
    )
    (comp (ref "U$63")
      (value "LP-FILTER/CAPACITOR/0603THIN")
      (footprint "eagle-import:LP-FILTER_CAPACITOR_0603_BOTTOM")
      (libsource (lib "eagle-import") (part "LP-FILTER/CAPACITOR/0603THIN"))
    )
    (comp (ref "U$64")
      (value "LP-FILTER/CAPACITOR/0603THIN")
      (footprint "eagle-import:LP-FILTER_CAPACITOR_0603_BOTTOM")
      (libsource (lib "eagle-import") (part "LP-FILTER/CAPACITOR/0603THIN"))
    )
    (comp (ref "U$65")
      (value "LP-FILTER/CAPACITOR/0603THIN")
      (footprint "eagle-import:LP-FILTER_CAPACITOR_0603_BOTTOM")
      (libsource (lib "eagle-import") (part "LP-FILTER/CAPACITOR/0603THIN"))
    )
    (comp (ref "U$66")
      (value "LP-FILTER/CAPACITOR/0603THIN")
      (footprint "eagle-import:LP-FILTER_CAPACITOR_0603_BOTTOM")
      (libsource (lib "eagle-import") (part "LP-FILTER/CAPACITOR/0603THIN"))
    )
    (comp (ref "U$67")
      (value "LP-FILTER/CAPACITOR/0603THIN")
      (footprint "eagle-import:LP-FILTER_CAPACITOR_0603_BOTTOM")
      (libsource (lib "eagle-import") (part "LP-FILTER/CAPACITOR/0603THIN"))
    )
    (comp (ref "U$68")
      (value "LP-FILTER/CAPACITOR/0603THIN")
      (footprint "eagle-import:LP-FILTER_CAPACITOR_0603_BOTTOM")
      (libsource (lib "eagle-import") (part "LP-FILTER/CAPACITOR/0603THIN"))
    )
    (comp (ref "U$69")
      (value "LP-FILTER/CAPACITOR/0603THIN")
      (footprint "eagle-import:LP-FILTER_CAPACITOR_0603_BOTTOM")
      (libsource (lib "eagle-import") (part "LP-FILTER/CAPACITOR/0603THIN"))
    )
    (comp (ref "U$70")
      (value "LP-FILTER/CAPACITOR/0603THIN")
      (footprint "eagle-import:LP-FILTER_CAPACITOR_0603_BOTTOM")
      (libsource (lib "eagle-import") (part "LP-FILTER/CAPACITOR/0603THIN"))
    )
    (comp (ref "U$71")
      (value "LP-FILTER/CAPACITOR/0603THIN")
      (footprint "eagle-import:LP-FILTER_CAPACITOR_0603_BOTTOM")
      (libsource (lib "eagle-import") (part "LP-FILTER/CAPACITOR/0603THIN"))
    )
    (comp (ref "U$72")
      (value "LP-FILTER/CAPACITOR/0603THIN")
      (footprint "eagle-import:LP-FILTER_CAPACITOR_0603_BOTTOM")
      (libsource (lib "eagle-import") (part "LP-FILTER/CAPACITOR/0603THIN"))
    )
    (comp (ref "U$73")
      (value "LP-FILTER/CAPACITOR/0603THIN")
      (footprint "eagle-import:LP-FILTER_CAPACITOR_0603_BOTTOM")
      (libsource (lib "eagle-import") (part "LP-FILTER/CAPACITOR/0603THIN"))
    )
    (comp (ref "U$74")
      (value "LP-FILTER/CAPACITOR/0603THIN")
      (footprint "eagle-import:LP-FILTER_CAPACITOR_0603_BOTTOM")
      (libsource (lib "eagle-import") (part "LP-FILTER/CAPACITOR/0603THIN"))
    )
    (comp (ref "U$75")
      (value "LP-FILTER/CAPACITOR/0603THIN")
      (footprint "eagle-import:LP-FILTER_CAPACITOR_0603_BOTTOM")
      (libsource (lib "eagle-import") (part "LP-FILTER/CAPACITOR/0603THIN"))
    )
    (comp (ref "U$76")
      (value "LP-FILTER/CAPACITOR/0603THIN")
      (footprint "eagle-import:LP-FILTER_CAPACITOR_0603_BOTTOM")
      (libsource (lib "eagle-import") (part "LP-FILTER/CAPACITOR/0603THIN"))
    )
    (comp (ref "U$77")
      (value "LP-FILTER/CAPACITOR/0603THIN")
      (footprint "eagle-import:LP-FILTER_CAPACITOR_0603_BOTTOM")
      (libsource (lib "eagle-import") (part "LP-FILTER/CAPACITOR/0603THIN"))
    )
    (comp (ref "U$78")
      (value "LP-FILTER/CAPACITOR/0603THIN")
      (footprint "eagle-import:LP-FILTER_CAPACITOR_0603_BOTTOM")
      (libsource (lib "eagle-import") (part "LP-FILTER/CAPACITOR/0603THIN"))
    )
    (comp (ref "U$79")
      (value "LP-FILTER/CAPACITOR/0603THIN")
      (footprint "eagle-import:LP-FILTER_CAPACITOR_0603_BOTTOM")
      (libsource (lib "eagle-import") (part "LP-FILTER/CAPACITOR/0603THIN"))
    )
    (comp (ref "U$80")
      (value "LP-FILTER/CAPACITOR/0603THIN")
      (footprint "eagle-import:LP-FILTER_CAPACITOR_0603_BOTTOM")
      (libsource (lib "eagle-import") (part "LP-FILTER/CAPACITOR/0603THIN"))
    )
    (comp (ref "U$81")
      (value "LP-FILTER/CAPACITOR/0603THIN")
      (footprint "eagle-import:LP-FILTER_CAPACITOR_0603_BOTTOM")
      (libsource (lib "eagle-import") (part "LP-FILTER/CAPACITOR/0603THIN"))
    )
    (comp (ref "U$82")
      (value "LP-FILTER/CAPACITOR/0603THIN")
      (footprint "eagle-import:LP-FILTER_CAPACITOR_0603_BOTTOM")
      (libsource (lib "eagle-import") (part "LP-FILTER/CAPACITOR/0603THIN"))
    )
    (comp (ref "U$83")
      (value "LP-FILTER/CAPACITOR/0603THIN")
      (footprint "eagle-import:LP-FILTER_CAPACITOR_0603_BOTTOM")
      (libsource (lib "eagle-import") (part "LP-FILTER/CAPACITOR/0603THIN"))
    )
    (comp (ref "U$84")
      (value "LP-FILTER/CAPACITOR/0603THIN")
      (footprint "eagle-import:LP-FILTER_CAPACITOR_0603_BOTTOM")
      (libsource (lib "eagle-import") (part "LP-FILTER/CAPACITOR/0603THIN"))
    )
    (comp (ref "U$85")
      (value "LP-FILTER/CAPACITOR/0603THIN")
      (footprint "eagle-import:LP-FILTER_CAPACITOR_0603_BOTTOM")
      (libsource (lib "eagle-import") (part "LP-FILTER/CAPACITOR/0603THIN"))
    )
    (comp (ref "U$86")
      (value "LP-FILTER/CAPACITOR/0603THIN")
      (footprint "eagle-import:LP-FILTER_CAPACITOR_0603_BOTTOM")
      (libsource (lib "eagle-import") (part "LP-FILTER/CAPACITOR/0603THIN"))
    )
    (comp (ref "U$87")
      (value "LP-FILTER/CAPACITOR/0603THIN")
      (footprint "eagle-import:LP-FILTER_CAPACITOR_0603_BOTTOM")
      (libsource (lib "eagle-import") (part "LP-FILTER/CAPACITOR/0603THIN"))
    )
    (comp (ref "U$88")
      (value "LP-FILTER/CAPACITOR/0603THIN")
      (footprint "eagle-import:LP-FILTER_CAPACITOR_0603_BOTTOM")
      (libsource (lib "eagle-import") (part "LP-FILTER/CAPACITOR/0603THIN"))
    )
    (comp (ref "U$89")
      (value "LP-FILTER/CAPACITOR/0603THIN")
      (footprint "eagle-import:LP-FILTER_CAPACITOR_0603_BOTTOM")
      (libsource (lib "eagle-import") (part "LP-FILTER/CAPACITOR/0603THIN"))
    )
    (comp (ref "X1")
      (value "RS180-3958")
      (footprint "eagle-import:SMDSMALL87758-5016")
      (libsource (lib "eagle-import") (part "87758-5016"))
    )
  )
  (nets
    (net (code "1") (name "/DC$01") (class "Default")
      (node (ref "J1") (pin "2") (pinfunction "2_2") (pintype "passive"))
      (node (ref "LP$1") (pin "$1") (pinfunction "IN_$1") (pintype "bidirectional"))
    )
    (net (code "2") (name "/DC$02") (class "Default")
      (node (ref "J1") (pin "4") (pinfunction "4_4") (pintype "passive"))
      (node (ref "LP$2") (pin "$1") (pinfunction "IN_$1") (pintype "bidirectional"))
    )
    (net (code "3") (name "/DC$03") (class "Default")
      (node (ref "J1") (pin "6") (pinfunction "6_6") (pintype "passive"))
      (node (ref "LP$3") (pin "$1") (pinfunction "IN_$1") (pintype "bidirectional"))
    )
    (net (code "4") (name "/DC$04") (class "Default")
      (node (ref "J1") (pin "8") (pinfunction "8_8") (pintype "passive"))
      (node (ref "LP$4") (pin "$1") (pinfunction "IN_$1") (pintype "bidirectional"))
    )
    (net (code "5") (name "/DC$05") (class "Default")
      (node (ref "J1") (pin "10") (pinfunction "10_10") (pintype "passive"))
      (node (ref "LP$5") (pin "$1") (pinfunction "IN_$1") (pintype "bidirectional"))
    )
    (net (code "6") (name "/DC$06") (class "Default")
      (node (ref "J1") (pin "12") (pinfunction "12_12") (pintype "passive"))
      (node (ref "LP$6") (pin "$1") (pinfunction "IN_$1") (pintype "bidirectional"))
    )
    (net (code "7") (name "/DC$07") (class "Default")
      (node (ref "J1") (pin "14") (pinfunction "14_14") (pintype "passive"))
      (node (ref "LP$7") (pin "$1") (pinfunction "IN_$1") (pintype "bidirectional"))
    )
    (net (code "8") (name "/DC$08") (class "Default")
      (node (ref "J1") (pin "16") (pinfunction "16_16") (pintype "passive"))
      (node (ref "LP$8") (pin "$1") (pinfunction "IN_$1") (pintype "bidirectional"))
    )
    (net (code "9") (name "/DC$09") (class "Default")
      (node (ref "J1") (pin "18") (pinfunction "18_18") (pintype "passive"))
      (node (ref "LP$9") (pin "$1") (pinfunction "IN_$1") (pintype "bidirectional"))
    )
    (net (code "10") (name "/DC$10") (class "Default")
      (node (ref "J1") (pin "20") (pinfunction "20_20") (pintype "passive"))
      (node (ref "LP$10") (pin "$1") (pinfunction "IN_$1") (pintype "bidirectional"))
    )
    (net (code "11") (name "/DC$11") (class "Default")
      (node (ref "J1") (pin "22") (pinfunction "22_22") (pintype "passive"))
      (node (ref "LP$11") (pin "$1") (pinfunction "IN_$1") (pintype "bidirectional"))
    )
    (net (code "12") (name "/DC$12") (class "Default")
      (node (ref "J1") (pin "24") (pinfunction "24_24") (pintype "passive"))
      (node (ref "LP$12") (pin "$1") (pinfunction "IN_$1") (pintype "bidirectional"))
    )
    (net (code "13") (name "/DC$13") (class "Default")
      (node (ref "J1") (pin "26") (pinfunction "26_26") (pintype "passive"))
      (node (ref "LP$13") (pin "$1") (pinfunction "IN_$1") (pintype "bidirectional"))
    )
    (net (code "14") (name "/DC$14") (class "Default")
      (node (ref "J1") (pin "28") (pinfunction "28_28") (pintype "passive"))
      (node (ref "LP$14") (pin "$1") (pinfunction "IN_$1") (pintype "bidirectional"))
    )
    (net (code "15") (name "/DC$15") (class "Default")
      (node (ref "J1") (pin "30") (pinfunction "30_30") (pintype "passive"))
      (node (ref "LP$15") (pin "$1") (pinfunction "IN_$1") (pintype "bidirectional"))
    )
    (net (code "16") (name "/DC$16") (class "Default")
      (node (ref "J1") (pin "32") (pinfunction "32_32") (pintype "passive"))
      (node (ref "LP$16") (pin "$1") (pinfunction "IN_$1") (pintype "bidirectional"))
    )
    (net (code "17") (name "/DC$17") (class "Default")
      (node (ref "J1") (pin "34") (pinfunction "34_34") (pintype "passive"))
      (node (ref "LP$17") (pin "$1") (pinfunction "IN_$1") (pintype "bidirectional"))
    )
    (net (code "18") (name "/DC$18") (class "Default")
      (node (ref "J1") (pin "36") (pinfunction "36_36") (pintype "passive"))
      (node (ref "LP$18") (pin "$1") (pinfunction "IN_$1") (pintype "bidirectional"))
    )
    (net (code "19") (name "/DC$19") (class "Default")
      (node (ref "J1") (pin "38") (pinfunction "38_38") (pintype "passive"))
      (node (ref "LP$19") (pin "$1") (pinfunction "IN_$1") (pintype "bidirectional"))
    )
    (net (code "20") (name "/DC$20") (class "Default")
      (node (ref "J1") (pin "40") (pinfunction "40_40") (pintype "passive"))
      (node (ref "LP$20") (pin "$1") (pinfunction "IN_$1") (pintype "bidirectional"))
    )
    (net (code "21") (name "/DC$21") (class "Default")
      (node (ref "J1") (pin "42") (pinfunction "42_42") (pintype "passive"))
      (node (ref "LP$21") (pin "$1") (pinfunction "IN_$1") (pintype "bidirectional"))
    )
    (net (code "22") (name "/DC$22") (class "Default")
      (node (ref "J1") (pin "44") (pinfunction "44_44") (pintype "passive"))
      (node (ref "LP$22") (pin "$1") (pinfunction "IN_$1") (pintype "bidirectional"))
    )
    (net (code "23") (name "/DC$23") (class "Default")
      (node (ref "J1") (pin "46") (pinfunction "46_46") (pintype "passive"))
      (node (ref "LP$23") (pin "$1") (pinfunction "IN_$1") (pintype "bidirectional"))
    )
    (net (code "24") (name "/DC$24") (class "Default")
      (node (ref "J1") (pin "48") (pinfunction "48_48") (pintype "passive"))
      (node (ref "LP$24") (pin "$1") (pinfunction "IN_$1") (pintype "bidirectional"))
    )
    (net (code "25") (name "/DC$25") (class "Default")
      (node (ref "J1") (pin "47") (pinfunction "47_47") (pintype "passive"))
      (node (ref "LP$25") (pin "$1") (pinfunction "IN_$1") (pintype "bidirectional"))
    )
    (net (code "26") (name "/DC$26") (class "Default")
      (node (ref "J1") (pin "45") (pinfunction "45_45") (pintype "passive"))
      (node (ref "LP$26") (pin "$1") (pinfunction "IN_$1") (pintype "bidirectional"))
    )
    (net (code "27") (name "/DC$27") (class "Default")
      (node (ref "J1") (pin "43") (pinfunction "43_43") (pintype "passive"))
      (node (ref "LP$27") (pin "$1") (pinfunction "IN_$1") (pintype "bidirectional"))
    )
    (net (code "28") (name "/DC$28") (class "Default")
      (node (ref "J1") (pin "41") (pinfunction "41_41") (pintype "passive"))
      (node (ref "LP$28") (pin "$1") (pinfunction "IN_$1") (pintype "bidirectional"))
    )
    (net (code "29") (name "/DC$29") (class "Default")
      (node (ref "J1") (pin "39") (pinfunction "39_39") (pintype "passive"))
      (node (ref "LP$29") (pin "$1") (pinfunction "IN_$1") (pintype "bidirectional"))
    )
    (net (code "30") (name "/DC$30") (class "Default")
      (node (ref "J1") (pin "37") (pinfunction "37_37") (pintype "passive"))
      (node (ref "LP$30") (pin "$1") (pinfunction "IN_$1") (pintype "bidirectional"))
    )
    (net (code "31") (name "/DC$31") (class "Default")
      (node (ref "J1") (pin "35") (pinfunction "35_35") (pintype "passive"))
      (node (ref "LP$31") (pin "$1") (pinfunction "IN_$1") (pintype "bidirectional"))
    )
    (net (code "32") (name "/DC$32") (class "Default")
      (node (ref "J1") (pin "33") (pinfunction "33_33") (pintype "passive"))
      (node (ref "LP$32") (pin "$1") (pinfunction "IN_$1") (pintype "bidirectional"))
    )
    (net (code "33") (name "/DC$33") (class "Default")
      (node (ref "J1") (pin "31") (pinfunction "31_31") (pintype "passive"))
      (node (ref "LP$33") (pin "$1") (pinfunction "IN_$1") (pintype "bidirectional"))
    )
    (net (code "34") (name "/DC$34") (class "Default")
      (node (ref "J1") (pin "29") (pinfunction "29_29") (pintype "passive"))
      (node (ref "LP$34") (pin "$1") (pinfunction "IN_$1") (pintype "bidirectional"))
    )
    (net (code "35") (name "/DC$35") (class "Default")
      (node (ref "J1") (pin "27") (pinfunction "27_27") (pintype "passive"))
      (node (ref "LP$35") (pin "$1") (pinfunction "IN_$1") (pintype "bidirectional"))
    )
    (net (code "36") (name "/DC$36") (class "Default")
      (node (ref "J1") (pin "25") (pinfunction "25_25") (pintype "passive"))
      (node (ref "LP$36") (pin "$1") (pinfunction "IN_$1") (pintype "bidirectional"))
    )
    (net (code "37") (name "/DC$37") (class "Default")
      (node (ref "J1") (pin "23") (pinfunction "23_23") (pintype "passive"))
      (node (ref "LP$37") (pin "$1") (pinfunction "IN_$1") (pintype "bidirectional"))
    )
    (net (code "38") (name "/DC$38") (class "Default")
      (node (ref "J1") (pin "21") (pinfunction "21_21") (pintype "passive"))
      (node (ref "LP$38") (pin "$1") (pinfunction "IN_$1") (pintype "bidirectional"))
    )
    (net (code "39") (name "/DC$39") (class "Default")
      (node (ref "J1") (pin "19") (pinfunction "19_19") (pintype "passive"))
      (node (ref "LP$39") (pin "$1") (pinfunction "IN_$1") (pintype "bidirectional"))
    )
    (net (code "40") (name "/DC$40") (class "Default")
      (node (ref "J1") (pin "17") (pinfunction "17_17") (pintype "passive"))
      (node (ref "LP$40") (pin "$1") (pinfunction "IN_$1") (pintype "bidirectional"))
    )
    (net (code "41") (name "/DC$41") (class "Default")
      (node (ref "J1") (pin "15") (pinfunction "15_15") (pintype "passive"))
      (node (ref "LP$41") (pin "$1") (pinfunction "IN_$1") (pintype "bidirectional"))
    )
    (net (code "42") (name "/DC$42") (class "Default")
      (node (ref "J1") (pin "13") (pinfunction "13_13") (pintype "passive"))
      (node (ref "LP$42") (pin "$1") (pinfunction "IN_$1") (pintype "bidirectional"))
    )
    (net (code "43") (name "/DC$43") (class "Default")
      (node (ref "J1") (pin "11") (pinfunction "11_11") (pintype "passive"))
      (node (ref "LP$43") (pin "$1") (pinfunction "IN_$1") (pintype "bidirectional"))
    )
    (net (code "44") (name "/DC$44") (class "Default")
      (node (ref "J1") (pin "9") (pinfunction "9_9") (pintype "passive"))
      (node (ref "LP$44") (pin "$1") (pinfunction "IN_$1") (pintype "bidirectional"))
    )
    (net (code "45") (name "/DC$45") (class "Default")
      (node (ref "J1") (pin "7") (pinfunction "7_7") (pintype "passive"))
      (node (ref "LP$45") (pin "$1") (pinfunction "IN_$1") (pintype "bidirectional"))
    )
    (net (code "46") (name "/DC$46") (class "Default")
      (node (ref "J1") (pin "5") (pinfunction "5_5") (pintype "passive"))
      (node (ref "LP$46") (pin "$1") (pinfunction "IN_$1") (pintype "bidirectional"))
    )
    (net (code "47") (name "/DC$47") (class "Default")
      (node (ref "J1") (pin "3") (pinfunction "3_3") (pintype "passive"))
      (node (ref "LP$47") (pin "$1") (pinfunction "IN_$1") (pintype "bidirectional"))
    )
    (net (code "48") (name "/DC$48") (class "Default")
      (node (ref "J1") (pin "1") (pinfunction "1_1") (pintype "passive"))
      (node (ref "LP$48") (pin "$1") (pinfunction "IN_$1") (pintype "bidirectional"))
    )
    (net (code "49") (name "/DCF$01") (class "Default")
      (node (ref "LP$1") (pin "$4") (pinfunction "OUT_$4") (pintype "bidirectional"))
      (node (ref "U$1") (pin "DC§1") (pinfunction "DC§01_DC§1") (pintype "bidirectional"))
      (node (ref "U$11") (pin "OUT1") (pinfunction "2_OUT1") (pintype "passive"))
      (node (ref "U$12") (pin "OUT") (pinfunction "2_OUT") (pintype "passive"))
      (node (ref "U$42") (pin "OUT") (pinfunction "2_OUT") (pintype "passive"))
      (node (ref "X1") (pin "P$1") (pinfunction "S_P$1") (pintype "passive"))
    )
    (net (code "50") (name "/DCF$02") (class "Default")
      (node (ref "LP$2") (pin "$4") (pinfunction "OUT_$4") (pintype "bidirectional"))
      (node (ref "U$1") (pin "DC§2") (pinfunction "DC§02_DC§2") (pintype "bidirectional"))
      (node (ref "U$43") (pin "OUT") (pinfunction "2_OUT") (pintype "passive"))
      (node (ref "X1") (pin "P$3") (pinfunction "S_P$3") (pintype "passive"))
    )
    (net (code "51") (name "/DCF$03") (class "Default")
      (node (ref "B$6") (pin "LF") (pinfunction "LF_LF") (pintype "bidirectional"))
      (node (ref "LP$3") (pin "$4") (pinfunction "OUT_$4") (pintype "bidirectional"))
      (node (ref "U$1") (pin "DC§3") (pinfunction "DC§03_DC§3") (pintype "bidirectional"))
      (node (ref "U$44") (pin "OUT") (pinfunction "2_OUT") (pintype "passive"))
      (node (ref "X1") (pin "P$5") (pinfunction "S_P$5") (pintype "passive"))
    )
    (net (code "52") (name "/DCF$04") (class "Default")
      (node (ref "B$11") (pin "LF") (pinfunction "LF_LF") (pintype "bidirectional"))
      (node (ref "LP$4") (pin "$4") (pinfunction "OUT_$4") (pintype "bidirectional"))
      (node (ref "U$1") (pin "DC§4") (pinfunction "DC§04_DC§4") (pintype "bidirectional"))
      (node (ref "U$45") (pin "OUT") (pinfunction "2_OUT") (pintype "passive"))
      (node (ref "X1") (pin "P$7") (pinfunction "S_P$7") (pintype "passive"))
    )
    (net (code "53") (name "/DCF$05") (class "Default")
      (node (ref "LP$5") (pin "$4") (pinfunction "OUT_$4") (pintype "bidirectional"))
      (node (ref "U$1") (pin "DC§5") (pinfunction "DC§05_DC§5") (pintype "bidirectional"))
      (node (ref "U$46") (pin "OUT") (pinfunction "2_OUT") (pintype "passive"))
      (node (ref "X1") (pin "P$9") (pinfunction "S_P$9") (pintype "passive"))
    )
    (net (code "54") (name "/DCF$06") (class "Default")
      (node (ref "B$2") (pin "LF") (pinfunction "LF_LF") (pintype "bidirectional"))
      (node (ref "LP$6") (pin "$4") (pinfunction "OUT_$4") (pintype "bidirectional"))
      (node (ref "U$1") (pin "DC§6") (pinfunction "DC§06_DC§6") (pintype "bidirectional"))
      (node (ref "U$47") (pin "OUT") (pinfunction "2_OUT") (pintype "passive"))
      (node (ref "X1") (pin "P$11") (pinfunction "S_P$11") (pintype "passive"))
    )
    (net (code "55") (name "/DCF$07") (class "Default")
      (node (ref "LP$7") (pin "$4") (pinfunction "OUT_$4") (pintype "bidirectional"))
      (node (ref "U$1") (pin "DC§7") (pinfunction "DC§07_DC§7") (pintype "bidirectional"))
      (node (ref "U$18") (pin "OUT1") (pinfunction "2_OUT1") (pintype "passive"))
      (node (ref "U$19") (pin "OUT") (pinfunction "2_OUT") (pintype "passive"))
      (node (ref "U$48") (pin "OUT") (pinfunction "2_OUT") (pintype "passive"))
      (node (ref "X1") (pin "P$13") (pinfunction "S_P$13") (pintype "passive"))
    )
    (net (code "56") (name "/DCF$08") (class "Default")
      (node (ref "B$12") (pin "LF") (pinfunction "LF_LF") (pintype "bidirectional"))
      (node (ref "LP$8") (pin "$4") (pinfunction "OUT_$4") (pintype "bidirectional"))
      (node (ref "U$1") (pin "DC§8") (pinfunction "DC§08_DC§8") (pintype "bidirectional"))
      (node (ref "U$49") (pin "OUT") (pinfunction "2_OUT") (pintype "passive"))
      (node (ref "X1") (pin "P$15") (pinfunction "S_P$15") (pintype "passive"))
    )
    (net (code "57") (name "/DCF$09") (class "Default")
      (node (ref "B$13") (pin "LF") (pinfunction "LF_LF") (pintype "bidirectional"))
      (node (ref "LP$9") (pin "$4") (pinfunction "OUT_$4") (pintype "bidirectional"))
      (node (ref "U$1") (pin "DC§9") (pinfunction "DC§09_DC§9") (pintype "bidirectional"))
      (node (ref "U$50") (pin "OUT") (pinfunction "2_OUT") (pintype "passive"))
      (node (ref "X1") (pin "P$17") (pinfunction "S_P$17") (pintype "passive"))
    )
    (net (code "58") (name "/DCF$10") (class "Default")
      (node (ref "LP$10") (pin "$4") (pinfunction "OUT_$4") (pintype "bidirectional"))
      (node (ref "U$1") (pin "DC§10") (pinfunction "DC§10_DC§10") (pintype "bidirectional"))
      (node (ref "U$51") (pin "OUT") (pinfunction "2_OUT") (pintype "passive"))
      (node (ref "X1") (pin "P$19") (pinfunction "S_P$19") (pintype "passive"))
    )
    (net (code "59") (name "/DCF$11") (class "Default")
      (node (ref "LP$11") (pin "$4") (pinfunction "OUT_$4") (pintype "bidirectional"))
      (node (ref "U$1") (pin "DC§11") (pinfunction "DC§11_DC§11") (pintype "bidirectional"))
      (node (ref "U$52") (pin "OUT") (pinfunction "2_OUT") (pintype "passive"))
      (node (ref "X1") (pin "P$21") (pinfunction "S_P$21") (pintype "passive"))
    )
    (net (code "60") (name "/DCF$12") (class "Default")
      (node (ref "B$3") (pin "LF") (pinfunction "LF_LF") (pintype "bidirectional"))
      (node (ref "LP$12") (pin "$4") (pinfunction "OUT_$4") (pintype "bidirectional"))
      (node (ref "U$1") (pin "DC§12") (pinfunction "DC§12_DC§12") (pintype "bidirectional"))
      (node (ref "U$53") (pin "OUT") (pinfunction "2_OUT") (pintype "passive"))
      (node (ref "X1") (pin "P$23") (pinfunction "S_P$23") (pintype "passive"))
    )
    (net (code "61") (name "/DCF$13") (class "Default")
      (node (ref "LP$13") (pin "$4") (pinfunction "OUT_$4") (pintype "bidirectional"))
      (node (ref "U$1") (pin "DC§13") (pinfunction "DC§13_DC§13") (pintype "bidirectional"))
      (node (ref "U$23") (pin "OUT1") (pinfunction "2_OUT1") (pintype "passive"))
      (node (ref "U$24") (pin "OUT") (pinfunction "2_OUT") (pintype "passive"))
      (node (ref "U$54") (pin "IN") (pinfunction "1_IN") (pintype "passive"))
      (node (ref "X1") (pin "P$25") (pinfunction "S_P$25") (pintype "passive"))
    )
    (net (code "62") (name "/DCF$14") (class "Default")
      (node (ref "LP$14") (pin "$4") (pinfunction "OUT_$4") (pintype "bidirectional"))
      (node (ref "U$1") (pin "DC§14") (pinfunction "DC§14_DC§14") (pintype "bidirectional"))
      (node (ref "U$55") (pin "IN") (pinfunction "1_IN") (pintype "passive"))
      (node (ref "X1") (pin "P$27") (pinfunction "S_P$27") (pintype "passive"))
    )
    (net (code "63") (name "/DCF$15") (class "Default")
      (node (ref "B$14") (pin "LF") (pinfunction "LF_LF") (pintype "bidirectional"))
      (node (ref "LP$15") (pin "$4") (pinfunction "OUT_$4") (pintype "bidirectional"))
      (node (ref "U$1") (pin "DC§15") (pinfunction "DC§15_DC§15") (pintype "bidirectional"))
      (node (ref "U$56") (pin "IN") (pinfunction "1_IN") (pintype "passive"))
      (node (ref "X1") (pin "P$29") (pinfunction "S_P$29") (pintype "passive"))
    )
    (net (code "64") (name "/DCF$16") (class "Default")
      (node (ref "B$15") (pin "LF") (pinfunction "LF_LF") (pintype "bidirectional"))
      (node (ref "LP$16") (pin "$4") (pinfunction "OUT_$4") (pintype "bidirectional"))
      (node (ref "U$1") (pin "DC§16") (pinfunction "DC§16_DC§16") (pintype "bidirectional"))
      (node (ref "U$57") (pin "IN") (pinfunction "1_IN") (pintype "passive"))
      (node (ref "X1") (pin "P$31") (pinfunction "S_P$31") (pintype "passive"))
    )
    (net (code "65") (name "/DCF$17") (class "Default")
      (node (ref "LP$17") (pin "$4") (pinfunction "OUT_$4") (pintype "bidirectional"))
      (node (ref "U$1") (pin "DC§17") (pinfunction "DC§17_DC§17") (pintype "bidirectional"))
      (node (ref "U$58") (pin "IN") (pinfunction "1_IN") (pintype "passive"))
      (node (ref "X1") (pin "P$33") (pinfunction "S_P$33") (pintype "passive"))
    )
    (net (code "66") (name "/DCF$18") (class "Default")
      (node (ref "B$4") (pin "LF") (pinfunction "LF_LF") (pintype "bidirectional"))
      (node (ref "LP$18") (pin "$4") (pinfunction "OUT_$4") (pintype "bidirectional"))
      (node (ref "U$1") (pin "DC§18") (pinfunction "DC§18_DC§18") (pintype "bidirectional"))
      (node (ref "U$59") (pin "IN") (pinfunction "1_IN") (pintype "passive"))
      (node (ref "X1") (pin "P$35") (pinfunction "S_P$35") (pintype "passive"))
    )
    (net (code "67") (name "/DCF$19") (class "Default")
      (node (ref "LP$19") (pin "$4") (pinfunction "OUT_$4") (pintype "bidirectional"))
      (node (ref "U$1") (pin "DC§19") (pinfunction "DC§019_DC§19") (pintype "bidirectional"))
      (node (ref "U$27") (pin "OUT1") (pinfunction "2_OUT1") (pintype "passive"))
      (node (ref "U$28") (pin "OUT") (pinfunction "2_OUT") (pintype "passive"))
      (node (ref "U$60") (pin "IN") (pinfunction "1_IN") (pintype "passive"))
      (node (ref "X1") (pin "P$37") (pinfunction "S_P$37") (pintype "passive"))
    )
    (net (code "68") (name "/DCF$20") (class "Default")
      (node (ref "B$16") (pin "LF") (pinfunction "LF_LF") (pintype "bidirectional"))
      (node (ref "LP$20") (pin "$4") (pinfunction "OUT_$4") (pintype "bidirectional"))
      (node (ref "U$1") (pin "DC§20") (pinfunction "DC§20_DC§20") (pintype "bidirectional"))
      (node (ref "U$61") (pin "IN") (pinfunction "1_IN") (pintype "passive"))
      (node (ref "X1") (pin "P$39") (pinfunction "S_P$39") (pintype "passive"))
    )
    (net (code "69") (name "/DCF$21") (class "Default")
      (node (ref "B$17") (pin "LF") (pinfunction "LF_LF") (pintype "bidirectional"))
      (node (ref "LP$21") (pin "$4") (pinfunction "OUT_$4") (pintype "bidirectional"))
      (node (ref "U$1") (pin "DC§21") (pinfunction "DC§21_DC§21") (pintype "bidirectional"))
      (node (ref "U$62") (pin "IN") (pinfunction "1_IN") (pintype "passive"))
      (node (ref "X1") (pin "P$41") (pinfunction "S_P$41") (pintype "passive"))
    )
    (net (code "70") (name "/DCF$22") (class "Default")
      (node (ref "LP$22") (pin "$4") (pinfunction "OUT_$4") (pintype "bidirectional"))
      (node (ref "U$1") (pin "DC§22") (pinfunction "DC§22_DC§22") (pintype "bidirectional"))
      (node (ref "U$63") (pin "IN") (pinfunction "1_IN") (pintype "passive"))
      (node (ref "X1") (pin "P$43") (pinfunction "S_P$43") (pintype "passive"))
    )
    (net (code "71") (name "/DCF$23") (class "Default")
      (node (ref "LP$23") (pin "$4") (pinfunction "OUT_$4") (pintype "bidirectional"))
      (node (ref "U$1") (pin "DC§23") (pinfunction "DC§23_DC§23") (pintype "bidirectional"))
      (node (ref "U$64") (pin "IN") (pinfunction "1_IN") (pintype "passive"))
      (node (ref "X1") (pin "P$45") (pinfunction "S_P$45") (pintype "passive"))
    )
    (net (code "72") (name "/DCF$24") (class "Default")
      (node (ref "B$5") (pin "LF") (pinfunction "LF_LF") (pintype "bidirectional"))
      (node (ref "LP$24") (pin "$4") (pinfunction "OUT_$4") (pintype "bidirectional"))
      (node (ref "U$1") (pin "DC§24") (pinfunction "DC§24_DC§24") (pintype "bidirectional"))
      (node (ref "U$65") (pin "IN") (pinfunction "1_IN") (pintype "passive"))
      (node (ref "X1") (pin "P$47") (pinfunction "S_P$47") (pintype "passive"))
    )
    (net (code "73") (name "/DCF$25") (class "Default")
      (node (ref "LP$25") (pin "$4") (pinfunction "OUT_$4") (pintype "bidirectional"))
      (node (ref "U$1") (pin "DC§25") (pinfunction "DC§025_DC§25") (pintype "bidirectional"))
      (node (ref "U$31") (pin "OUT1") (pinfunction "2_OUT1") (pintype "passive"))
      (node (ref "U$32") (pin "OUT") (pinfunction "2_OUT") (pintype "passive"))
      (node (ref "U$66") (pin "IN") (pinfunction "1_IN") (pintype "passive"))
      (node (ref "X1") (pin "P$48") (pinfunction "S_P$48") (pintype "passive"))
    )
    (net (code "74") (name "/DCF$26") (class "Default")
      (node (ref "LP$26") (pin "$4") (pinfunction "OUT_$4") (pintype "bidirectional"))
      (node (ref "U$1") (pin "DC§26") (pinfunction "DC§026_DC§26") (pintype "bidirectional"))
      (node (ref "U$67") (pin "IN") (pinfunction "1_IN") (pintype "passive"))
      (node (ref "X1") (pin "P$46") (pinfunction "S_P$46") (pintype "passive"))
    )
    (net (code "75") (name "/DCF$27") (class "Default")
      (node (ref "B$10") (pin "LF") (pinfunction "LF_LF") (pintype "bidirectional"))
      (node (ref "LP$27") (pin "$4") (pinfunction "OUT_$4") (pintype "bidirectional"))
      (node (ref "U$1") (pin "DC§27") (pinfunction "DC§027_DC§27") (pintype "bidirectional"))
      (node (ref "U$68") (pin "IN") (pinfunction "1_IN") (pintype "passive"))
      (node (ref "X1") (pin "P$44") (pinfunction "S_P$44") (pintype "passive"))
    )
    (net (code "76") (name "/DCF$28") (class "Default")
      (node (ref "B$18") (pin "LF") (pinfunction "LF_LF") (pintype "bidirectional"))
      (node (ref "LP$28") (pin "$4") (pinfunction "OUT_$4") (pintype "bidirectional"))
      (node (ref "U$1") (pin "DC§28") (pinfunction "DC§028_DC§28") (pintype "bidirectional"))
      (node (ref "U$69") (pin "IN") (pinfunction "1_IN") (pintype "passive"))
      (node (ref "X1") (pin "P$42") (pinfunction "S_P$42") (pintype "passive"))
    )
    (net (code "77") (name "/DCF$29") (class "Default")
      (node (ref "LP$29") (pin "$4") (pinfunction "OUT_$4") (pintype "bidirectional"))
      (node (ref "U$1") (pin "DC§29") (pinfunction "DC§029_DC§29") (pintype "bidirectional"))
      (node (ref "U$70") (pin "IN") (pinfunction "1_IN") (pintype "passive"))
      (node (ref "X1") (pin "P$40") (pinfunction "S_P$40") (pintype "passive"))
    )
    (net (code "78") (name "/DCF$30") (class "Default")
      (node (ref "B$8") (pin "LF") (pinfunction "LF_LF") (pintype "bidirectional"))
      (node (ref "LP$30") (pin "$4") (pinfunction "OUT_$4") (pintype "bidirectional"))
      (node (ref "U$1") (pin "DC§30") (pinfunction "DC§030_DC§30") (pintype "bidirectional"))
      (node (ref "U$71") (pin "IN") (pinfunction "1_IN") (pintype "passive"))
      (node (ref "X1") (pin "P$38") (pinfunction "S_P$38") (pintype "passive"))
    )
    (net (code "79") (name "/DCF$31") (class "Default")
      (node (ref "LP$31") (pin "$4") (pinfunction "OUT_$4") (pintype "bidirectional"))
      (node (ref "U$1") (pin "DC§31") (pinfunction "DC§031_DC§31") (pintype "bidirectional"))
      (node (ref "U$35") (pin "OUT1") (pinfunction "2_OUT1") (pintype "passive"))
      (node (ref "U$36") (pin "OUT") (pinfunction "2_OUT") (pintype "passive"))
      (node (ref "U$72") (pin "IN") (pinfunction "1_IN") (pintype "passive"))
      (node (ref "X1") (pin "P$36") (pinfunction "S_P$36") (pintype "passive"))
    )
    (net (code "80") (name "/DCF$32") (class "Default")
      (node (ref "B$19") (pin "LF") (pinfunction "LF_LF") (pintype "bidirectional"))
      (node (ref "LP$32") (pin "$4") (pinfunction "OUT_$4") (pintype "bidirectional"))
      (node (ref "U$1") (pin "DC§32") (pinfunction "DC§032_DC§32") (pintype "bidirectional"))
      (node (ref "U$73") (pin "IN") (pinfunction "1_IN") (pintype "passive"))
      (node (ref "X1") (pin "P$34") (pinfunction "S_P$34") (pintype "passive"))
    )
    (net (code "81") (name "/DCF$33") (class "Default")
      (node (ref "B$20") (pin "LF") (pinfunction "LF_LF") (pintype "bidirectional"))
      (node (ref "LP$33") (pin "$4") (pinfunction "OUT_$4") (pintype "bidirectional"))
      (node (ref "U$1") (pin "DC§33") (pinfunction "DC§033_DC§33") (pintype "bidirectional"))
      (node (ref "U$74") (pin "IN") (pinfunction "1_IN") (pintype "passive"))
      (node (ref "X1") (pin "P$32") (pinfunction "S_P$32") (pintype "passive"))
    )
    (net (code "82") (name "/DCF$34") (class "Default")
      (node (ref "LP$34") (pin "$4") (pinfunction "OUT_$4") (pintype "bidirectional"))
      (node (ref "U$1") (pin "DC§34") (pinfunction "DC§034_DC§34") (pintype "bidirectional"))
      (node (ref "U$75") (pin "IN") (pinfunction "1_IN") (pintype "passive"))
      (node (ref "X1") (pin "P$30") (pinfunction "S_P$30") (pintype "passive"))
    )
    (net (code "83") (name "/DCF$35") (class "Default")
      (node (ref "LP$35") (pin "$4") (pinfunction "OUT_$4") (pintype "bidirectional"))
      (node (ref "U$1") (pin "DC§35") (pinfunction "DC§035_DC§35") (pintype "bidirectional"))
      (node (ref "U$76") (pin "IN") (pinfunction "1_IN") (pintype "passive"))
      (node (ref "X1") (pin "P$28") (pinfunction "S_P$28") (pintype "passive"))
    )
    (net (code "84") (name "/DCF$36") (class "Default")
      (node (ref "B$9") (pin "LF") (pinfunction "LF_LF") (pintype "bidirectional"))
      (node (ref "LP$36") (pin "$4") (pinfunction "OUT_$4") (pintype "bidirectional"))
      (node (ref "U$1") (pin "DC§36") (pinfunction "DC§036_DC§36") (pintype "bidirectional"))
      (node (ref "U$77") (pin "IN") (pinfunction "1_IN") (pintype "passive"))
      (node (ref "X1") (pin "P$26") (pinfunction "S_P$26") (pintype "passive"))
    )
    (net (code "85") (name "/DCF$37") (class "Default")
      (node (ref "LP$37") (pin "$4") (pinfunction "OUT_$4") (pintype "bidirectional"))
      (node (ref "U$1") (pin "DC§37") (pinfunction "DC§037_DC§37") (pintype "bidirectional"))
      (node (ref "U$39") (pin "OUT1") (pinfunction "2_OUT1") (pintype "passive"))
      (node (ref "U$40") (pin "OUT") (pinfunction "2_OUT") (pintype "passive"))
      (node (ref "U$78") (pin "IN") (pinfunction "1_IN") (pintype "passive"))
      (node (ref "X1") (pin "P$24") (pinfunction "S_P$24") (pintype "passive"))
    )
    (net (code "86") (name "/DCF$38") (class "Default")
      (node (ref "LP$38") (pin "$4") (pinfunction "OUT_$4") (pintype "bidirectional"))
      (node (ref "U$1") (pin "DC§38") (pinfunction "DC§038_DC§38") (pintype "bidirectional"))
      (node (ref "U$79") (pin "IN") (pinfunction "1_IN") (pintype "passive"))
      (node (ref "X1") (pin "P$22") (pinfunction "S_P$22") (pintype "passive"))
    )
    (net (code "87") (name "/DCF$39") (class "Default")
      (node (ref "B$21") (pin "LF") (pinfunction "LF_LF") (pintype "bidirectional"))
      (node (ref "LP$39") (pin "$4") (pinfunction "OUT_$4") (pintype "bidirectional"))
      (node (ref "U$1") (pin "DC§39") (pinfunction "DC§039_DC§39") (pintype "bidirectional"))
      (node (ref "U$80") (pin "IN") (pinfunction "1_IN") (pintype "passive"))
      (node (ref "X1") (pin "P$20") (pinfunction "S_P$20") (pintype "passive"))
    )
    (net (code "88") (name "/DCF$40") (class "Default")
      (node (ref "B$22") (pin "LF") (pinfunction "LF_LF") (pintype "bidirectional"))
      (node (ref "LP$40") (pin "$4") (pinfunction "OUT_$4") (pintype "bidirectional"))
      (node (ref "U$1") (pin "DC§40") (pinfunction "DC§040_DC§40") (pintype "bidirectional"))
      (node (ref "U$81") (pin "IN") (pinfunction "1_IN") (pintype "passive"))
      (node (ref "X1") (pin "P$18") (pinfunction "S_P$18") (pintype "passive"))
    )
    (net (code "89") (name "/DCF$41") (class "Default")
      (node (ref "LP$41") (pin "$4") (pinfunction "OUT_$4") (pintype "bidirectional"))
      (node (ref "U$1") (pin "DC§41") (pinfunction "DC§041_DC§41") (pintype "bidirectional"))
      (node (ref "U$82") (pin "IN") (pinfunction "1_IN") (pintype "passive"))
      (node (ref "X1") (pin "P$16") (pinfunction "S_P$16") (pintype "passive"))
    )
    (net (code "90") (name "/DCF$42") (class "Default")
      (node (ref "B$7") (pin "LF") (pinfunction "LF_LF") (pintype "bidirectional"))
      (node (ref "LP$42") (pin "$4") (pinfunction "OUT_$4") (pintype "bidirectional"))
      (node (ref "U$1") (pin "DC§42") (pinfunction "DC§042_DC§42") (pintype "bidirectional"))
      (node (ref "U$83") (pin "IN") (pinfunction "1_IN") (pintype "passive"))
      (node (ref "X1") (pin "P$14") (pinfunction "S_P$14") (pintype "passive"))
    )
    (net (code "91") (name "/DCF$43") (class "Default")
      (node (ref "LP$43") (pin "$4") (pinfunction "OUT_$4") (pintype "bidirectional"))
      (node (ref "U$1") (pin "DC§43") (pinfunction "DC§043_DC§43") (pintype "bidirectional"))
      (node (ref "U$14") (pin "OUT1") (pinfunction "2_OUT1") (pintype "passive"))
      (node (ref "U$15") (pin "OUT") (pinfunction "2_OUT") (pintype "passive"))
      (node (ref "U$84") (pin "IN") (pinfunction "1_IN") (pintype "passive"))
      (node (ref "X1") (pin "P$12") (pinfunction "S_P$12") (pintype "passive"))
    )
    (net (code "92") (name "/DCF$44") (class "Default")
      (node (ref "B$23") (pin "LF") (pinfunction "LF_LF") (pintype "bidirectional"))
      (node (ref "LP$44") (pin "$4") (pinfunction "OUT_$4") (pintype "bidirectional"))
      (node (ref "U$1") (pin "DC§44") (pinfunction "DC§044_DC§44") (pintype "bidirectional"))
      (node (ref "U$85") (pin "IN") (pinfunction "1_IN") (pintype "passive"))
      (node (ref "X1") (pin "P$10") (pinfunction "S_P$10") (pintype "passive"))
    )
    (net (code "93") (name "/DCF$45") (class "Default")
      (node (ref "B$24") (pin "LF") (pinfunction "LF_LF") (pintype "bidirectional"))
      (node (ref "LP$45") (pin "$4") (pinfunction "OUT_$4") (pintype "bidirectional"))
      (node (ref "U$1") (pin "DC§45") (pinfunction "DC§045_DC§45") (pintype "bidirectional"))
      (node (ref "U$86") (pin "IN") (pinfunction "1_IN") (pintype "passive"))
      (node (ref "X1") (pin "P$8") (pinfunction "S_P$8") (pintype "passive"))
    )
    (net (code "94") (name "/DCF$46") (class "Default")
      (node (ref "LP$46") (pin "$4") (pinfunction "OUT_$4") (pintype "bidirectional"))
      (node (ref "U$1") (pin "DC§46") (pinfunction "DC§046_DC§46") (pintype "bidirectional"))
      (node (ref "U$87") (pin "IN") (pinfunction "1_IN") (pintype "passive"))
      (node (ref "X1") (pin "P$6") (pinfunction "S_P$6") (pintype "passive"))
    )
    (net (code "95") (name "/DCF$47") (class "Default")
      (node (ref "LP$47") (pin "$4") (pinfunction "OUT_$4") (pintype "bidirectional"))
      (node (ref "U$1") (pin "DC§47") (pinfunction "DC§047_DC§47") (pintype "bidirectional"))
      (node (ref "U$88") (pin "IN") (pinfunction "1_IN") (pintype "passive"))
      (node (ref "X1") (pin "P$4") (pinfunction "S_P$4") (pintype "passive"))
    )
    (net (code "96") (name "/DCF$48") (class "Default")
      (node (ref "B$1") (pin "LF") (pinfunction "LF_LF") (pintype "bidirectional"))
      (node (ref "LP$48") (pin "$4") (pinfunction "OUT_$4") (pintype "bidirectional"))
      (node (ref "U$1") (pin "DC§48") (pinfunction "DC§048_DC§48") (pintype "bidirectional"))
      (node (ref "U$89") (pin "IN") (pinfunction "1_IN") (pintype "passive"))
      (node (ref "X1") (pin "P$2") (pinfunction "S_P$2") (pintype "passive"))
    )
    (net (code "97") (name "/RF$R1") (class "Default")
      (node (ref "L$3") (pin "OUT") (pinfunction "OUT_OUT") (pintype "passive"))
      (node (ref "U$1") (pin "RF$06_R1") (pinfunction "RF$06_R1_RF$06_R1") (pintype "bidirectional"))
      (node (ref "U$18") (pin "OUT") (pinfunction "1_OUT") (pintype "passive"))
    )
    (net (code "98") (name "/RF$R2") (class "Default")
      (node (ref "L$4") (pin "OUT") (pinfunction "OUT_OUT") (pintype "passive"))
      (node (ref "U$1") (pin "RF$12_R2") (pinfunction "RF$12_R2_RF$12_R2") (pintype "bidirectional"))
      (node (ref "U$23") (pin "OUT") (pinfunction "1_OUT") (pintype "passive"))
    )
    (net (code "99") (name "/RF$R3") (class "Default")
      (node (ref "L$5") (pin "OUT") (pinfunction "OUT_OUT") (pintype "passive"))
      (node (ref "U$1") (pin "RF$18_R3") (pinfunction "RF$18_R3_RF$18_R3") (pintype "bidirectional"))
      (node (ref "U$27") (pin "OUT") (pinfunction "1_OUT") (pintype "passive"))
    )
    (net (code "100") (name "/RF$R4") (class "Default")
      (node (ref "L$6") (pin "OUT") (pinfunction "OUT_OUT") (pintype "passive"))
      (node (ref "U$1") (pin "RF$24_R4") (pinfunction "RF$24_R4_RF$24_R4") (pintype "bidirectional"))
      (node (ref "U$31") (pin "OUT") (pinfunction "1_OUT") (pintype "passive"))
    )
    (net (code "101") (name "/RF$R5") (class "Default")
      (node (ref "L$7") (pin "OUT") (pinfunction "OUT_OUT") (pintype "passive"))
      (node (ref "U$1") (pin "RF$30_R5") (pinfunction "RF$30_R5_RF$30_R5") (pintype "bidirectional"))
      (node (ref "U$35") (pin "OUT") (pinfunction "1_OUT") (pintype "passive"))
    )
    (net (code "102") (name "/RF$R6") (class "Default")
      (node (ref "L$8") (pin "OUT") (pinfunction "OUT_OUT") (pintype "passive"))
      (node (ref "U$1") (pin "RF$36_R6") (pinfunction "RF$36_R6_RF$36_R6") (pintype "bidirectional"))
      (node (ref "U$39") (pin "OUT") (pinfunction "1_OUT") (pintype "passive"))
    )
    (net (code "103") (name "/RF$R7") (class "Default")
      (node (ref "L$1") (pin "OUT") (pinfunction "OUT_OUT") (pintype "passive"))
      (node (ref "U$1") (pin "RF$42_R7") (pinfunction "RF$42_R7_RF$42_R7") (pintype "bidirectional"))
      (node (ref "U$14") (pin "OUT") (pinfunction "1_OUT") (pintype "passive"))
    )
    (net (code "104") (name "/RF$R8") (class "Default")
      (node (ref "L$2") (pin "OUT") (pinfunction "OUT_OUT") (pintype "passive"))
      (node (ref "U$1") (pin "RF$48_R8") (pinfunction "RF$48_R8_RF$48_R8") (pintype "bidirectional"))
      (node (ref "U$11") (pin "OUT") (pinfunction "1_OUT") (pintype "passive"))
    )
    (net (code "105") (name "GND") (class "Default")
      (node (ref "J1") (pin "49") (pinfunction "49_49") (pintype "passive"))
      (node (ref "J1") (pin "50") (pinfunction "50_50") (pintype "passive"))
      (node (ref "J1") (pin "51") (pinfunction "51_51") (pintype "passive"))
      (node (ref "J1") (pin "52") (pinfunction "52_52") (pintype "passive"))
      (node (ref "J1") (pin "53") (pinfunction "53_53") (pintype "passive"))
      (node (ref "J1") (pin "54") (pinfunction "54_54") (pintype "passive"))
      (node (ref "J1") (pin "55") (pinfunction "55_55") (pintype "passive"))
      (node (ref "J1") (pin "56") (pinfunction "56_56") (pintype "passive"))
      (node (ref "J1") (pin "57") (pinfunction "57_57") (pintype "passive"))
      (node (ref "J1") (pin "58") (pinfunction "58_58") (pintype "passive"))
      (node (ref "J1") (pin "59") (pinfunction "59_59") (pintype "passive"))
      (node (ref "J1") (pin "60") (pinfunction "60_60") (pintype "passive"))
      (node (ref "LP$1") (pin "$6") (pinfunction "GND_$6") (pintype "bidirectional"))
      (node (ref "LP$10") (pin "$6") (pinfunction "GND_$6") (pintype "bidirectional"))
      (node (ref "LP$11") (pin "$6") (pinfunction "GND_$6") (pintype "bidirectional"))
      (node (ref "LP$12") (pin "$6") (pinfunction "GND_$6") (pintype "bidirectional"))
      (node (ref "LP$13") (pin "$6") (pinfunction "GND_$6") (pintype "bidirectional"))
      (node (ref "LP$14") (pin "$6") (pinfunction "GND_$6") (pintype "bidirectional"))
      (node (ref "LP$15") (pin "$6") (pinfunction "GND_$6") (pintype "bidirectional"))
      (node (ref "LP$16") (pin "$6") (pinfunction "GND_$6") (pintype "bidirectional"))
      (node (ref "LP$17") (pin "$6") (pinfunction "GND_$6") (pintype "bidirectional"))
      (node (ref "LP$18") (pin "$6") (pinfunction "GND_$6") (pintype "bidirectional"))
      (node (ref "LP$19") (pin "$6") (pinfunction "GND_$6") (pintype "bidirectional"))
      (node (ref "LP$2") (pin "$6") (pinfunction "GND_$6") (pintype "bidirectional"))
      (node (ref "LP$20") (pin "$6") (pinfunction "GND_$6") (pintype "bidirectional"))
      (node (ref "LP$21") (pin "$6") (pinfunction "GND_$6") (pintype "bidirectional"))
      (node (ref "LP$22") (pin "$6") (pinfunction "GND_$6") (pintype "bidirectional"))
      (node (ref "LP$23") (pin "$6") (pinfunction "GND_$6") (pintype "bidirectional"))
      (node (ref "LP$24") (pin "$6") (pinfunction "GND_$6") (pintype "bidirectional"))
      (node (ref "LP$25") (pin "$6") (pinfunction "GND_$6") (pintype "bidirectional"))
      (node (ref "LP$26") (pin "$6") (pinfunction "GND_$6") (pintype "bidirectional"))
      (node (ref "LP$27") (pin "$6") (pinfunction "GND_$6") (pintype "bidirectional"))
      (node (ref "LP$28") (pin "$6") (pinfunction "GND_$6") (pintype "bidirectional"))
      (node (ref "LP$29") (pin "$6") (pinfunction "GND_$6") (pintype "bidirectional"))
      (node (ref "LP$3") (pin "$6") (pinfunction "GND_$6") (pintype "bidirectional"))
      (node (ref "LP$30") (pin "$6") (pinfunction "GND_$6") (pintype "bidirectional"))
      (node (ref "LP$31") (pin "$6") (pinfunction "GND_$6") (pintype "bidirectional"))
      (node (ref "LP$32") (pin "$6") (pinfunction "GND_$6") (pintype "bidirectional"))
      (node (ref "LP$33") (pin "$6") (pinfunction "GND_$6") (pintype "bidirectional"))
      (node (ref "LP$34") (pin "$6") (pinfunction "GND_$6") (pintype "bidirectional"))
      (node (ref "LP$35") (pin "$6") (pinfunction "GND_$6") (pintype "bidirectional"))
      (node (ref "LP$36") (pin "$6") (pinfunction "GND_$6") (pintype "bidirectional"))
      (node (ref "LP$37") (pin "$6") (pinfunction "GND_$6") (pintype "bidirectional"))
      (node (ref "LP$38") (pin "$6") (pinfunction "GND_$6") (pintype "bidirectional"))
      (node (ref "LP$39") (pin "$6") (pinfunction "GND_$6") (pintype "bidirectional"))
      (node (ref "LP$4") (pin "$6") (pinfunction "GND_$6") (pintype "bidirectional"))
      (node (ref "LP$40") (pin "$6") (pinfunction "GND_$6") (pintype "bidirectional"))
      (node (ref "LP$41") (pin "$6") (pinfunction "GND_$6") (pintype "bidirectional"))
      (node (ref "LP$42") (pin "$6") (pinfunction "GND_$6") (pintype "bidirectional"))
      (node (ref "LP$43") (pin "$6") (pinfunction "GND_$6") (pintype "bidirectional"))
      (node (ref "LP$44") (pin "$6") (pinfunction "GND_$6") (pintype "bidirectional"))
      (node (ref "LP$45") (pin "$6") (pinfunction "GND_$6") (pintype "bidirectional"))
      (node (ref "LP$46") (pin "$6") (pinfunction "GND_$6") (pintype "bidirectional"))
      (node (ref "LP$47") (pin "$6") (pinfunction "GND_$6") (pintype "bidirectional"))
      (node (ref "LP$48") (pin "$6") (pinfunction "GND_$6") (pintype "bidirectional"))
      (node (ref "LP$5") (pin "$6") (pinfunction "GND_$6") (pintype "bidirectional"))
      (node (ref "LP$6") (pin "$6") (pinfunction "GND_$6") (pintype "bidirectional"))
      (node (ref "LP$7") (pin "$6") (pinfunction "GND_$6") (pintype "bidirectional"))
      (node (ref "LP$8") (pin "$6") (pinfunction "GND_$6") (pintype "bidirectional"))
      (node (ref "LP$9") (pin "$6") (pinfunction "GND_$6") (pintype "bidirectional"))
      (node (ref "S$1") (pin "2@1") (pinfunction "GND_2@1") (pintype "passive"))
      (node (ref "S$1") (pin "2@2") (pinfunction "GND_2@2") (pintype "passive"))
      (node (ref "S$10") (pin "2@1") (pinfunction "GND_2@1") (pintype "passive"))
      (node (ref "S$10") (pin "2@2") (pinfunction "GND_2@2") (pintype "passive"))
      (node (ref "S$11") (pin "2@1") (pinfunction "GND_2@1") (pintype "passive"))
      (node (ref "S$11") (pin "2@2") (pinfunction "GND_2@2") (pintype "passive"))
      (node (ref "S$12") (pin "2@1") (pinfunction "GND_2@1") (pintype "passive"))
      (node (ref "S$12") (pin "2@2") (pinfunction "GND_2@2") (pintype "passive"))
      (node (ref "S$13") (pin "2@1") (pinfunction "GND_2@1") (pintype "passive"))
      (node (ref "S$13") (pin "2@2") (pinfunction "GND_2@2") (pintype "passive"))
      (node (ref "S$14") (pin "2@1") (pinfunction "GND_2@1") (pintype "passive"))
      (node (ref "S$14") (pin "2@2") (pinfunction "GND_2@2") (pintype "passive"))
      (node (ref "S$15") (pin "2@1") (pinfunction "GND_2@1") (pintype "passive"))
      (node (ref "S$15") (pin "2@2") (pinfunction "GND_2@2") (pintype "passive"))
      (node (ref "S$16") (pin "2@1") (pinfunction "GND_2@1") (pintype "passive"))
      (node (ref "S$16") (pin "2@2") (pinfunction "GND_2@2") (pintype "passive"))
      (node (ref "S$17") (pin "2@1") (pinfunction "GND_2@1") (pintype "passive"))
      (node (ref "S$17") (pin "2@2") (pinfunction "GND_2@2") (pintype "passive"))
      (node (ref "S$2") (pin "2@1") (pinfunction "GND_2@1") (pintype "passive"))
      (node (ref "S$2") (pin "2@2") (pinfunction "GND_2@2") (pintype "passive"))
      (node (ref "S$3") (pin "2@1") (pinfunction "GND_2@1") (pintype "passive"))
      (node (ref "S$3") (pin "2@2") (pinfunction "GND_2@2") (pintype "passive"))
      (node (ref "S$4") (pin "2@1") (pinfunction "GND_2@1") (pintype "passive"))
      (node (ref "S$4") (pin "2@2") (pinfunction "GND_2@2") (pintype "passive"))
      (node (ref "S$5") (pin "2@1") (pinfunction "GND_2@1") (pintype "passive"))
      (node (ref "S$5") (pin "2@2") (pinfunction "GND_2@2") (pintype "passive"))
      (node (ref "S$6") (pin "2@1") (pinfunction "GND_2@1") (pintype "passive"))
      (node (ref "S$6") (pin "2@2") (pinfunction "GND_2@2") (pintype "passive"))
      (node (ref "S$7") (pin "2@1") (pinfunction "GND_2@1") (pintype "passive"))
      (node (ref "S$7") (pin "2@2") (pinfunction "GND_2@2") (pintype "passive"))
      (node (ref "S$8") (pin "2@1") (pinfunction "GND_2@1") (pintype "passive"))
      (node (ref "S$8") (pin "2@2") (pinfunction "GND_2@2") (pintype "passive"))
      (node (ref "S$9") (pin "2@1") (pinfunction "GND_2@1") (pintype "passive"))
      (node (ref "S$9") (pin "2@2") (pinfunction "GND_2@2") (pintype "passive"))
      (node (ref "U$10") (pin "OUT") (pinfunction "2_OUT") (pintype "passive"))
      (node (ref "U$12") (pin "IN") (pinfunction "1_IN") (pintype "passive"))
      (node (ref "U$15") (pin "IN") (pinfunction "1_IN") (pintype "passive"))
      (node (ref "U$16") (pin "OUT") (pinfunction "2_OUT") (pintype "passive"))
      (node (ref "U$19") (pin "IN") (pinfunction "1_IN") (pintype "passive"))
      (node (ref "U$21") (pin "OUT") (pinfunction "2_OUT") (pintype "passive"))
      (node (ref "U$22") (pin "OUT") (pinfunction "2_OUT") (pintype "passive"))
      (node (ref "U$24") (pin "IN") (pinfunction "1_IN") (pintype "passive"))
      (node (ref "U$28") (pin "IN") (pinfunction "1_IN") (pintype "passive"))
      (node (ref "U$30") (pin "OUT") (pinfunction "2_OUT") (pintype "passive"))
      (node (ref "U$32") (pin "IN") (pinfunction "1_IN") (pintype "passive"))
      (node (ref "U$34") (pin "OUT") (pinfunction "2_OUT") (pintype "passive"))
      (node (ref "U$36") (pin "IN") (pinfunction "1_IN") (pintype "passive"))
      (node (ref "U$38") (pin "OUT") (pinfunction "2_OUT") (pintype "passive"))
      (node (ref "U$40") (pin "IN") (pinfunction "1_IN") (pintype "passive"))
      (node (ref "U$42") (pin "IN") (pinfunction "1_IN") (pintype "passive"))
      (node (ref "U$43") (pin "IN") (pinfunction "1_IN") (pintype "passive"))
      (node (ref "U$44") (pin "IN") (pinfunction "1_IN") (pintype "passive"))
      (node (ref "U$45") (pin "IN") (pinfunction "1_IN") (pintype "passive"))
      (node (ref "U$46") (pin "IN") (pinfunction "1_IN") (pintype "passive"))
      (node (ref "U$47") (pin "IN") (pinfunction "1_IN") (pintype "passive"))
      (node (ref "U$48") (pin "IN") (pinfunction "1_IN") (pintype "passive"))
      (node (ref "U$49") (pin "IN") (pinfunction "1_IN") (pintype "passive"))
      (node (ref "U$50") (pin "IN") (pinfunction "1_IN") (pintype "passive"))
      (node (ref "U$51") (pin "IN") (pinfunction "1_IN") (pintype "passive"))
      (node (ref "U$52") (pin "IN") (pinfunction "1_IN") (pintype "passive"))
      (node (ref "U$53") (pin "IN") (pinfunction "1_IN") (pintype "passive"))
      (node (ref "U$54") (pin "OUT") (pinfunction "2_OUT") (pintype "passive"))
      (node (ref "U$55") (pin "OUT") (pinfunction "2_OUT") (pintype "passive"))
      (node (ref "U$56") (pin "OUT") (pinfunction "2_OUT") (pintype "passive"))
      (node (ref "U$57") (pin "OUT") (pinfunction "2_OUT") (pintype "passive"))
      (node (ref "U$58") (pin "OUT") (pinfunction "2_OUT") (pintype "passive"))
      (node (ref "U$59") (pin "OUT") (pinfunction "2_OUT") (pintype "passive"))
      (node (ref "U$60") (pin "OUT") (pinfunction "2_OUT") (pintype "passive"))
      (node (ref "U$61") (pin "OUT") (pinfunction "2_OUT") (pintype "passive"))
      (node (ref "U$62") (pin "OUT") (pinfunction "2_OUT") (pintype "passive"))
      (node (ref "U$63") (pin "OUT") (pinfunction "2_OUT") (pintype "passive"))
      (node (ref "U$64") (pin "OUT") (pinfunction "2_OUT") (pintype "passive"))
      (node (ref "U$65") (pin "OUT") (pinfunction "2_OUT") (pintype "passive"))
      (node (ref "U$66") (pin "OUT") (pinfunction "2_OUT") (pintype "passive"))
      (node (ref "U$67") (pin "OUT") (pinfunction "2_OUT") (pintype "passive"))
      (node (ref "U$68") (pin "OUT") (pinfunction "2_OUT") (pintype "passive"))
      (node (ref "U$69") (pin "OUT") (pinfunction "2_OUT") (pintype "passive"))
      (node (ref "U$7") (pin "OUT") (pinfunction "2_OUT") (pintype "passive"))
      (node (ref "U$70") (pin "OUT") (pinfunction "2_OUT") (pintype "passive"))
      (node (ref "U$71") (pin "OUT") (pinfunction "2_OUT") (pintype "passive"))
      (node (ref "U$72") (pin "OUT") (pinfunction "2_OUT") (pintype "passive"))
      (node (ref "U$73") (pin "OUT") (pinfunction "2_OUT") (pintype "passive"))
      (node (ref "U$74") (pin "OUT") (pinfunction "2_OUT") (pintype "passive"))
      (node (ref "U$75") (pin "OUT") (pinfunction "2_OUT") (pintype "passive"))
      (node (ref "U$76") (pin "OUT") (pinfunction "2_OUT") (pintype "passive"))
      (node (ref "U$77") (pin "OUT") (pinfunction "2_OUT") (pintype "passive"))
      (node (ref "U$78") (pin "OUT") (pinfunction "2_OUT") (pintype "passive"))
      (node (ref "U$79") (pin "OUT") (pinfunction "2_OUT") (pintype "passive"))
      (node (ref "U$80") (pin "OUT") (pinfunction "2_OUT") (pintype "passive"))
      (node (ref "U$81") (pin "OUT") (pinfunction "2_OUT") (pintype "passive"))
      (node (ref "U$82") (pin "OUT") (pinfunction "2_OUT") (pintype "passive"))
      (node (ref "U$83") (pin "OUT") (pinfunction "2_OUT") (pintype "passive"))
      (node (ref "U$84") (pin "OUT") (pinfunction "2_OUT") (pintype "passive"))
      (node (ref "U$85") (pin "OUT") (pinfunction "2_OUT") (pintype "passive"))
      (node (ref "U$86") (pin "OUT") (pinfunction "2_OUT") (pintype "passive"))
      (node (ref "U$87") (pin "OUT") (pinfunction "2_OUT") (pintype "passive"))
      (node (ref "U$88") (pin "OUT") (pinfunction "2_OUT") (pintype "passive"))
      (node (ref "U$89") (pin "OUT") (pinfunction "2_OUT") (pintype "passive"))
      (node (ref "X1") (pin "P$49") (pinfunction "S_P$49") (pintype "passive"))
      (node (ref "X1") (pin "P$50") (pinfunction "S_P$50") (pintype "passive"))
    )
    (net (code "106") (name "Net-(B$6-PadHF)") (class "Default")
      (node (ref "B$6") (pin "HF") (pinfunction "HF_HF") (pintype "bidirectional"))
      (node (ref "S$1") (pin "1") (pinfunction "1_1") (pintype "passive"))
    )
    (net (code "107") (name "Net-(B$6-PadOUT)") (class "Default")
      (node (ref "B$6") (pin "OUT") (pinfunction "OUT_OUT") (pintype "bidirectional"))
      (node (ref "U$1") (pin "RF$03_G1") (pinfunction "RF$03_G1_RF$03_G1") (pintype "bidirectional"))
    )
    (net (code "108") (name "Net-(B$10-PadHF)") (class "Default")
      (node (ref "B$10") (pin "HF") (pinfunction "HF_HF") (pintype "bidirectional"))
      (node (ref "S$2") (pin "1") (pinfunction "1_1") (pintype "passive"))
    )
    (net (code "109") (name "Net-(B$10-PadOUT)") (class "Default")
      (node (ref "B$10") (pin "OUT") (pinfunction "OUT_OUT") (pintype "bidirectional"))
      (node (ref "U$1") (pin "RF$27_G9") (pinfunction "RF$27_G9_RF$27_G9") (pintype "bidirectional"))
    )
    (net (code "110") (name "Net-(B$11-PadHF)") (class "Default")
      (node (ref "B$11") (pin "HF") (pinfunction "HF_HF") (pintype "bidirectional"))
      (node (ref "S$8") (pin "1") (pinfunction "1_1") (pintype "passive"))
    )
    (net (code "111") (name "Net-(B$11-PadOUT)") (class "Default")
      (node (ref "B$11") (pin "OUT") (pinfunction "OUT_OUT") (pintype "bidirectional"))
      (node (ref "U$1") (pin "RF$04_G2") (pinfunction "RF$04_G2_RF$04_G2") (pintype "bidirectional"))
    )
    (net (code "112") (name "Net-(B$12-PadHF)") (class "Default")
      (node (ref "B$12") (pin "HF") (pinfunction "HF_HF") (pintype "bidirectional"))
      (node (ref "S$9") (pin "1") (pinfunction "1_1") (pintype "passive"))
    )
    (net (code "113") (name "Net-(B$12-PadOUT)") (class "Default")
      (node (ref "B$12") (pin "OUT") (pinfunction "OUT_OUT") (pintype "bidirectional"))
      (node (ref "U$1") (pin "RF$08_G3") (pinfunction "RF$08_G3_RF$08_G3") (pintype "bidirectional"))
    )
    (net (code "114") (name "Net-(B$13-PadHF)") (class "Default")
      (node (ref "B$13") (pin "HF") (pinfunction "HF_HF") (pintype "bidirectional"))
      (node (ref "S$10") (pin "1") (pinfunction "1_1") (pintype "passive"))
    )
    (net (code "115") (name "Net-(B$13-PadOUT)") (class "Default")
      (node (ref "B$13") (pin "OUT") (pinfunction "OUT_OUT") (pintype "bidirectional"))
      (node (ref "U$1") (pin "RF$09_G4") (pinfunction "RF$09_G4_RF$09_G4") (pintype "bidirectional"))
    )
    (net (code "116") (name "Net-(B$14-PadHF)") (class "Default")
      (node (ref "B$14") (pin "HF") (pinfunction "HF_HF") (pintype "bidirectional"))
      (node (ref "S$11") (pin "1") (pinfunction "1_1") (pintype "passive"))
    )
    (net (code "117") (name "Net-(B$14-PadOUT)") (class "Default")
      (node (ref "B$14") (pin "OUT") (pinfunction "OUT_OUT") (pintype "bidirectional"))
      (node (ref "U$1") (pin "RF$15_G5") (pinfunction "RF$15_G5_RF$15_G5") (pintype "bidirectional"))
    )
    (net (code "118") (name "Net-(B$15-PadHF)") (class "Default")
      (node (ref "B$15") (pin "HF") (pinfunction "HF_HF") (pintype "bidirectional"))
      (node (ref "S$12") (pin "1") (pinfunction "1_1") (pintype "passive"))
    )
    (net (code "119") (name "Net-(B$15-PadOUT)") (class "Default")
      (node (ref "B$15") (pin "OUT") (pinfunction "OUT_OUT") (pintype "bidirectional"))
      (node (ref "U$1") (pin "RF$16_G6") (pinfunction "RF$16_G6_RF$16_G6") (pintype "bidirectional"))
    )
    (net (code "120") (name "Net-(B$16-PadHF)") (class "Default")
      (node (ref "B$16") (pin "HF") (pinfunction "HF_HF") (pintype "bidirectional"))
      (node (ref "S$13") (pin "1") (pinfunction "1_1") (pintype "passive"))
    )
    (net (code "121") (name "Net-(B$16-PadOUT)") (class "Default")
      (node (ref "B$16") (pin "OUT") (pinfunction "OUT_OUT") (pintype "bidirectional"))
      (node (ref "U$1") (pin "RF$20_G7") (pinfunction "RF$20_G7_RF$20_G7") (pintype "bidirectional"))
    )
    (net (code "122") (name "Net-(B$17-PadHF)") (class "Default")
      (node (ref "B$17") (pin "HF") (pinfunction "HF_HF") (pintype "bidirectional"))
      (node (ref "S$14") (pin "1") (pinfunction "1_1") (pintype "passive"))
    )
    (net (code "123") (name "Net-(B$17-PadOUT)") (class "Default")
      (node (ref "B$17") (pin "OUT") (pinfunction "OUT_OUT") (pintype "bidirectional"))
      (node (ref "U$1") (pin "RF$21_G8") (pinfunction "RF$21_G8_RF$21_G8") (pintype "bidirectional"))
    )
    (net (code "124") (name "Net-(B$18-PadHF)") (class "Default")
      (node (ref "B$18") (pin "HF") (pinfunction "HF_HF") (pintype "bidirectional"))
      (node (ref "S$3") (pin "1") (pinfunction "1_1") (pintype "passive"))
    )
    (net (code "125") (name "Net-(B$18-PadOUT)") (class "Default")
      (node (ref "B$18") (pin "OUT") (pinfunction "OUT_OUT") (pintype "bidirectional"))
      (node (ref "U$1") (pin "RF$28_G10") (pinfunction "RF$28_G10_RF$28_G10") (pintype "bidirectional"))
    )
    (net (code "126") (name "Net-(B$19-PadHF)") (class "Default")
      (node (ref "B$19") (pin "HF") (pinfunction "HF_HF") (pintype "bidirectional"))
      (node (ref "S$4") (pin "1") (pinfunction "1_1") (pintype "passive"))
    )
    (net (code "127") (name "Net-(B$19-PadOUT)") (class "Default")
      (node (ref "B$19") (pin "OUT") (pinfunction "OUT_OUT") (pintype "bidirectional"))
      (node (ref "U$1") (pin "RF$32_G11") (pinfunction "RF$32_G11_RF$32_G11") (pintype "bidirectional"))
    )
    (net (code "128") (name "Net-(B$20-PadHF)") (class "Default")
      (node (ref "B$20") (pin "HF") (pinfunction "HF_HF") (pintype "bidirectional"))
      (node (ref "S$6") (pin "1") (pinfunction "1_1") (pintype "passive"))
    )
    (net (code "129") (name "Net-(B$20-PadOUT)") (class "Default")
      (node (ref "B$20") (pin "OUT") (pinfunction "OUT_OUT") (pintype "bidirectional"))
      (node (ref "U$1") (pin "RF$33_G12") (pinfunction "RF$33_G12_RF$33_G12") (pintype "bidirectional"))
    )
    (net (code "130") (name "Net-(B$21-PadHF)") (class "Default")
      (node (ref "B$21") (pin "HF") (pinfunction "HF_HF") (pintype "bidirectional"))
      (node (ref "S$7") (pin "1") (pinfunction "1_1") (pintype "passive"))
    )
    (net (code "131") (name "Net-(B$21-PadOUT)") (class "Default")
      (node (ref "B$21") (pin "OUT") (pinfunction "OUT_OUT") (pintype "bidirectional"))
      (node (ref "U$1") (pin "RF$39_G13") (pinfunction "RF$39_G13_RF$39_G13") (pintype "bidirectional"))
    )
    (net (code "132") (name "Net-(B$22-PadHF)") (class "Default")
      (node (ref "B$22") (pin "HF") (pinfunction "HF_HF") (pintype "bidirectional"))
      (node (ref "S$15") (pin "1") (pinfunction "1_1") (pintype "passive"))
    )
    (net (code "133") (name "Net-(B$22-PadOUT)") (class "Default")
      (node (ref "B$22") (pin "OUT") (pinfunction "OUT_OUT") (pintype "bidirectional"))
      (node (ref "U$1") (pin "RF$40_G14") (pinfunction "RF$40_G14_RF$40_G14") (pintype "bidirectional"))
    )
    (net (code "134") (name "Net-(B$23-PadHF)") (class "Default")
      (node (ref "B$23") (pin "HF") (pinfunction "HF_HF") (pintype "bidirectional"))
      (node (ref "S$16") (pin "1") (pinfunction "1_1") (pintype "passive"))
    )
    (net (code "135") (name "Net-(B$23-PadOUT)") (class "Default")
      (node (ref "B$23") (pin "OUT") (pinfunction "OUT_OUT") (pintype "bidirectional"))
      (node (ref "U$1") (pin "RF$44_G15") (pinfunction "RF$44_G15_RF$44_G15") (pintype "bidirectional"))
    )
    (net (code "136") (name "Net-(B$24-PadHF)") (class "Default")
      (node (ref "B$24") (pin "HF") (pinfunction "HF_HF") (pintype "bidirectional"))
      (node (ref "S$17") (pin "1") (pinfunction "1_1") (pintype "passive"))
    )
    (net (code "137") (name "Net-(B$24-PadOUT)") (class "Default")
      (node (ref "B$24") (pin "OUT") (pinfunction "OUT_OUT") (pintype "bidirectional"))
      (node (ref "U$1") (pin "RF$45_G16") (pinfunction "RF$45_G16_RF$45_G16") (pintype "bidirectional"))
    )
    (net (code "138") (name "Net-(U$2-IN)") (class "Default")
      (node (ref "U$2") (pin "P$1") (pinfunction "IN_P$1") (pintype "bidirectional"))
      (node (ref "U$3") (pin "P$2") (pinfunction "OUT1_P$2") (pintype "bidirectional"))
    )
    (net (code "139") (name "Net-(U$2-OUT1)") (class "Default")
      (node (ref "B$1") (pin "HF") (pinfunction "HF_HF") (pintype "bidirectional"))
      (node (ref "U$2") (pin "P$2") (pinfunction "OUT1_P$2") (pintype "bidirectional"))
    )
    (net (code "140") (name "Net-(U$2-OUT2)") (class "Default")
      (node (ref "B$7") (pin "HF") (pinfunction "HF_HF") (pintype "bidirectional"))
      (node (ref "U$2") (pin "P$3") (pinfunction "OUT2_P$3") (pintype "bidirectional"))
    )
    (net (code "141") (name "Net-(U$3-IN)") (class "Default")
      (node (ref "U$3") (pin "P$1") (pinfunction "IN_P$1") (pintype "bidirectional"))
      (node (ref "U$4") (pin "P$2") (pinfunction "OUT1_P$2") (pintype "bidirectional"))
    )
    (net (code "142") (name "Net-(U$3-OUT2)") (class "Default")
      (node (ref "U$3") (pin "P$3") (pinfunction "OUT2_P$3") (pintype "bidirectional"))
      (node (ref "U$9") (pin "P$1") (pinfunction "IN_P$1") (pintype "bidirectional"))
    )
    (net (code "143") (name "Net-(U$4-IN)") (class "Default")
      (node (ref "S$5") (pin "1") (pinfunction "1_1") (pintype "passive"))
      (node (ref "U$4") (pin "P$1") (pinfunction "IN_P$1") (pintype "bidirectional"))
    )
    (net (code "144") (name "Net-(U$4-OUT2)") (class "Default")
      (node (ref "U$4") (pin "P$3") (pinfunction "OUT2_P$3") (pintype "bidirectional"))
      (node (ref "U$5") (pin "P$1") (pinfunction "IN_P$1") (pintype "bidirectional"))
    )
    (net (code "145") (name "Net-(U$5-OUT1)") (class "Default")
      (node (ref "U$5") (pin "P$2") (pinfunction "OUT1_P$2") (pintype "bidirectional"))
      (node (ref "U$8") (pin "P$1") (pinfunction "IN_P$1") (pintype "bidirectional"))
    )
    (net (code "146") (name "Net-(U$5-OUT2)") (class "Default")
      (node (ref "U$5") (pin "P$3") (pinfunction "OUT2_P$3") (pintype "bidirectional"))
      (node (ref "U$6") (pin "P$1") (pinfunction "IN_P$1") (pintype "bidirectional"))
    )
    (net (code "147") (name "Net-(U$6-OUT1)") (class "Default")
      (node (ref "B$3") (pin "HF") (pinfunction "HF_HF") (pintype "bidirectional"))
      (node (ref "U$6") (pin "P$2") (pinfunction "OUT1_P$2") (pintype "bidirectional"))
    )
    (net (code "148") (name "Net-(U$6-OUT2)") (class "Default")
      (node (ref "B$2") (pin "HF") (pinfunction "HF_HF") (pintype "bidirectional"))
      (node (ref "U$6") (pin "P$3") (pinfunction "OUT2_P$3") (pintype "bidirectional"))
    )
    (net (code "149") (name "Net-(U$8-OUT1)") (class "Default")
      (node (ref "B$5") (pin "HF") (pinfunction "HF_HF") (pintype "bidirectional"))
      (node (ref "U$8") (pin "P$2") (pinfunction "OUT1_P$2") (pintype "bidirectional"))
    )
    (net (code "150") (name "Net-(U$8-OUT2)") (class "Default")
      (node (ref "B$4") (pin "HF") (pinfunction "HF_HF") (pintype "bidirectional"))
      (node (ref "U$8") (pin "P$3") (pinfunction "OUT2_P$3") (pintype "bidirectional"))
    )
    (net (code "151") (name "Net-(U$9-OUT1)") (class "Default")
      (node (ref "B$9") (pin "HF") (pinfunction "HF_HF") (pintype "bidirectional"))
      (node (ref "U$9") (pin "P$2") (pinfunction "OUT1_P$2") (pintype "bidirectional"))
    )
    (net (code "152") (name "Net-(U$9-OUT2)") (class "Default")
      (node (ref "B$8") (pin "HF") (pinfunction "HF_HF") (pintype "bidirectional"))
      (node (ref "U$9") (pin "P$3") (pinfunction "OUT2_P$3") (pintype "bidirectional"))
    )
    (net (code "153") (name "Net-(U$10-1)") (class "Default")
      (node (ref "B$1") (pin "OUT") (pinfunction "OUT_OUT") (pintype "bidirectional"))
      (node (ref "U$10") (pin "IN") (pinfunction "1_IN") (pintype "passive"))
      (node (ref "U$13") (pin "OUT") (pinfunction "2_OUT") (pintype "passive"))
    )
    (net (code "154") (name "Net-(U$13-1)") (class "Default")
      (node (ref "L$2") (pin "IN") (pinfunction "IN_IN") (pintype "passive"))
      (node (ref "U$13") (pin "IN") (pinfunction "1_IN") (pintype "passive"))
    )
    (net (code "155") (name "Net-(U$16-1)") (class "Default")
      (node (ref "B$2") (pin "OUT") (pinfunction "OUT_OUT") (pintype "bidirectional"))
      (node (ref "U$16") (pin "IN") (pinfunction "1_IN") (pintype "passive"))
      (node (ref "U$20") (pin "OUT") (pinfunction "2_OUT") (pintype "passive"))
    )
    (net (code "156") (name "Net-(U$17-1)") (class "Default")
      (node (ref "L$1") (pin "IN") (pinfunction "IN_IN") (pintype "passive"))
      (node (ref "U$17") (pin "IN") (pinfunction "1_IN") (pintype "passive"))
    )
    (net (code "157") (name "Net-(U$17-2)") (class "Default")
      (node (ref "B$7") (pin "OUT") (pinfunction "OUT_OUT") (pintype "bidirectional"))
      (node (ref "U$17") (pin "OUT") (pinfunction "2_OUT") (pintype "passive"))
      (node (ref "U$7") (pin "IN") (pinfunction "1_IN") (pintype "passive"))
    )
    (net (code "158") (name "Net-(U$20-1)") (class "Default")
      (node (ref "L$3") (pin "IN") (pinfunction "IN_IN") (pintype "passive"))
      (node (ref "U$20") (pin "IN") (pinfunction "1_IN") (pintype "passive"))
    )
    (net (code "159") (name "Net-(U$21-1)") (class "Default")
      (node (ref "B$4") (pin "OUT") (pinfunction "OUT_OUT") (pintype "bidirectional"))
      (node (ref "U$21") (pin "IN") (pinfunction "1_IN") (pintype "passive"))
      (node (ref "U$29") (pin "OUT") (pinfunction "2_OUT") (pintype "passive"))
    )
    (net (code "160") (name "Net-(U$22-1)") (class "Default")
      (node (ref "B$3") (pin "OUT") (pinfunction "OUT_OUT") (pintype "bidirectional"))
      (node (ref "U$22") (pin "IN") (pinfunction "1_IN") (pintype "passive"))
      (node (ref "U$26") (pin "OUT") (pinfunction "2_OUT") (pintype "passive"))
    )
    (net (code "161") (name "Net-(U$26-1)") (class "Default")
      (node (ref "L$4") (pin "IN") (pinfunction "IN_IN") (pintype "passive"))
      (node (ref "U$26") (pin "IN") (pinfunction "1_IN") (pintype "passive"))
    )
    (net (code "162") (name "Net-(U$29-1)") (class "Default")
      (node (ref "L$5") (pin "IN") (pinfunction "IN_IN") (pintype "passive"))
      (node (ref "U$29") (pin "IN") (pinfunction "1_IN") (pintype "passive"))
    )
    (net (code "163") (name "Net-(U$30-1)") (class "Default")
      (node (ref "B$5") (pin "OUT") (pinfunction "OUT_OUT") (pintype "bidirectional"))
      (node (ref "U$30") (pin "IN") (pinfunction "1_IN") (pintype "passive"))
      (node (ref "U$33") (pin "OUT") (pinfunction "2_OUT") (pintype "passive"))
    )
    (net (code "164") (name "Net-(U$33-1)") (class "Default")
      (node (ref "L$6") (pin "IN") (pinfunction "IN_IN") (pintype "passive"))
      (node (ref "U$33") (pin "IN") (pinfunction "1_IN") (pintype "passive"))
    )
    (net (code "165") (name "Net-(U$34-1)") (class "Default")
      (node (ref "B$8") (pin "OUT") (pinfunction "OUT_OUT") (pintype "bidirectional"))
      (node (ref "U$34") (pin "IN") (pinfunction "1_IN") (pintype "passive"))
      (node (ref "U$37") (pin "OUT") (pinfunction "2_OUT") (pintype "passive"))
    )
    (net (code "166") (name "Net-(U$37-1)") (class "Default")
      (node (ref "L$7") (pin "IN") (pinfunction "IN_IN") (pintype "passive"))
      (node (ref "U$37") (pin "IN") (pinfunction "1_IN") (pintype "passive"))
    )
    (net (code "167") (name "Net-(U$38-1)") (class "Default")
      (node (ref "B$9") (pin "OUT") (pinfunction "OUT_OUT") (pintype "bidirectional"))
      (node (ref "U$38") (pin "IN") (pinfunction "1_IN") (pintype "passive"))
      (node (ref "U$41") (pin "OUT") (pinfunction "2_OUT") (pintype "passive"))
    )
    (net (code "168") (name "Net-(U$41-1)") (class "Default")
      (node (ref "L$8") (pin "IN") (pinfunction "IN_IN") (pintype "passive"))
      (node (ref "U$41") (pin "IN") (pinfunction "1_IN") (pintype "passive"))
    )
    (net (code "169") (name "unconnected-(U$1-PadRF$GND)") (class "Default")
      (node (ref "U$1") (pin "RF$GND") (pinfunction "RF$GND_RF$GND") (pintype "bidirectional"))
    )
    (net (code "170") (name "unconnected-(U$1-PadRF$GND1)") (class "Default")
      (node (ref "U$1") (pin "RF$GND1") (pinfunction "RF$GND1_RF$GND1") (pintype "bidirectional"))
    )
    (net (code "171") (name "unconnected-(U$1-PadRF$GND2)") (class "Default")
      (node (ref "U$1") (pin "RF$GND2") (pinfunction "RF$GND2_RF$GND2") (pintype "bidirectional"))
    )
    (net (code "172") (name "unconnected-(U$1-PadRF$GND3)") (class "Default")
      (node (ref "U$1") (pin "RF$GND3") (pinfunction "RF$GND3_RF$GND3") (pintype "bidirectional"))
    )
    (net (code "173") (name "unconnected-(U$1-PadRF$GND4)") (class "Default")
      (node (ref "U$1") (pin "RF$GND4") (pinfunction "RF$GND4_RF$GND4") (pintype "bidirectional"))
    )
    (net (code "174") (name "unconnected-(U$1-PadRF$GND5)") (class "Default")
      (node (ref "U$1") (pin "RF$GND5") (pinfunction "RF$GND5_RF$GND5") (pintype "bidirectional"))
    )
    (net (code "175") (name "unconnected-(U$1-PadRF$GND6)") (class "Default")
      (node (ref "U$1") (pin "RF$GND6") (pinfunction "RF$GND6_RF$GND6") (pintype "bidirectional"))
    )
    (net (code "176") (name "unconnected-(U$1-PadRF$GND7)") (class "Default")
      (node (ref "U$1") (pin "RF$GND7") (pinfunction "RF$GND7_RF$GND7") (pintype "bidirectional"))
    )
  )
)
